# 20160428.net
KiCad netlist of a schematic drawn in Altium Designer
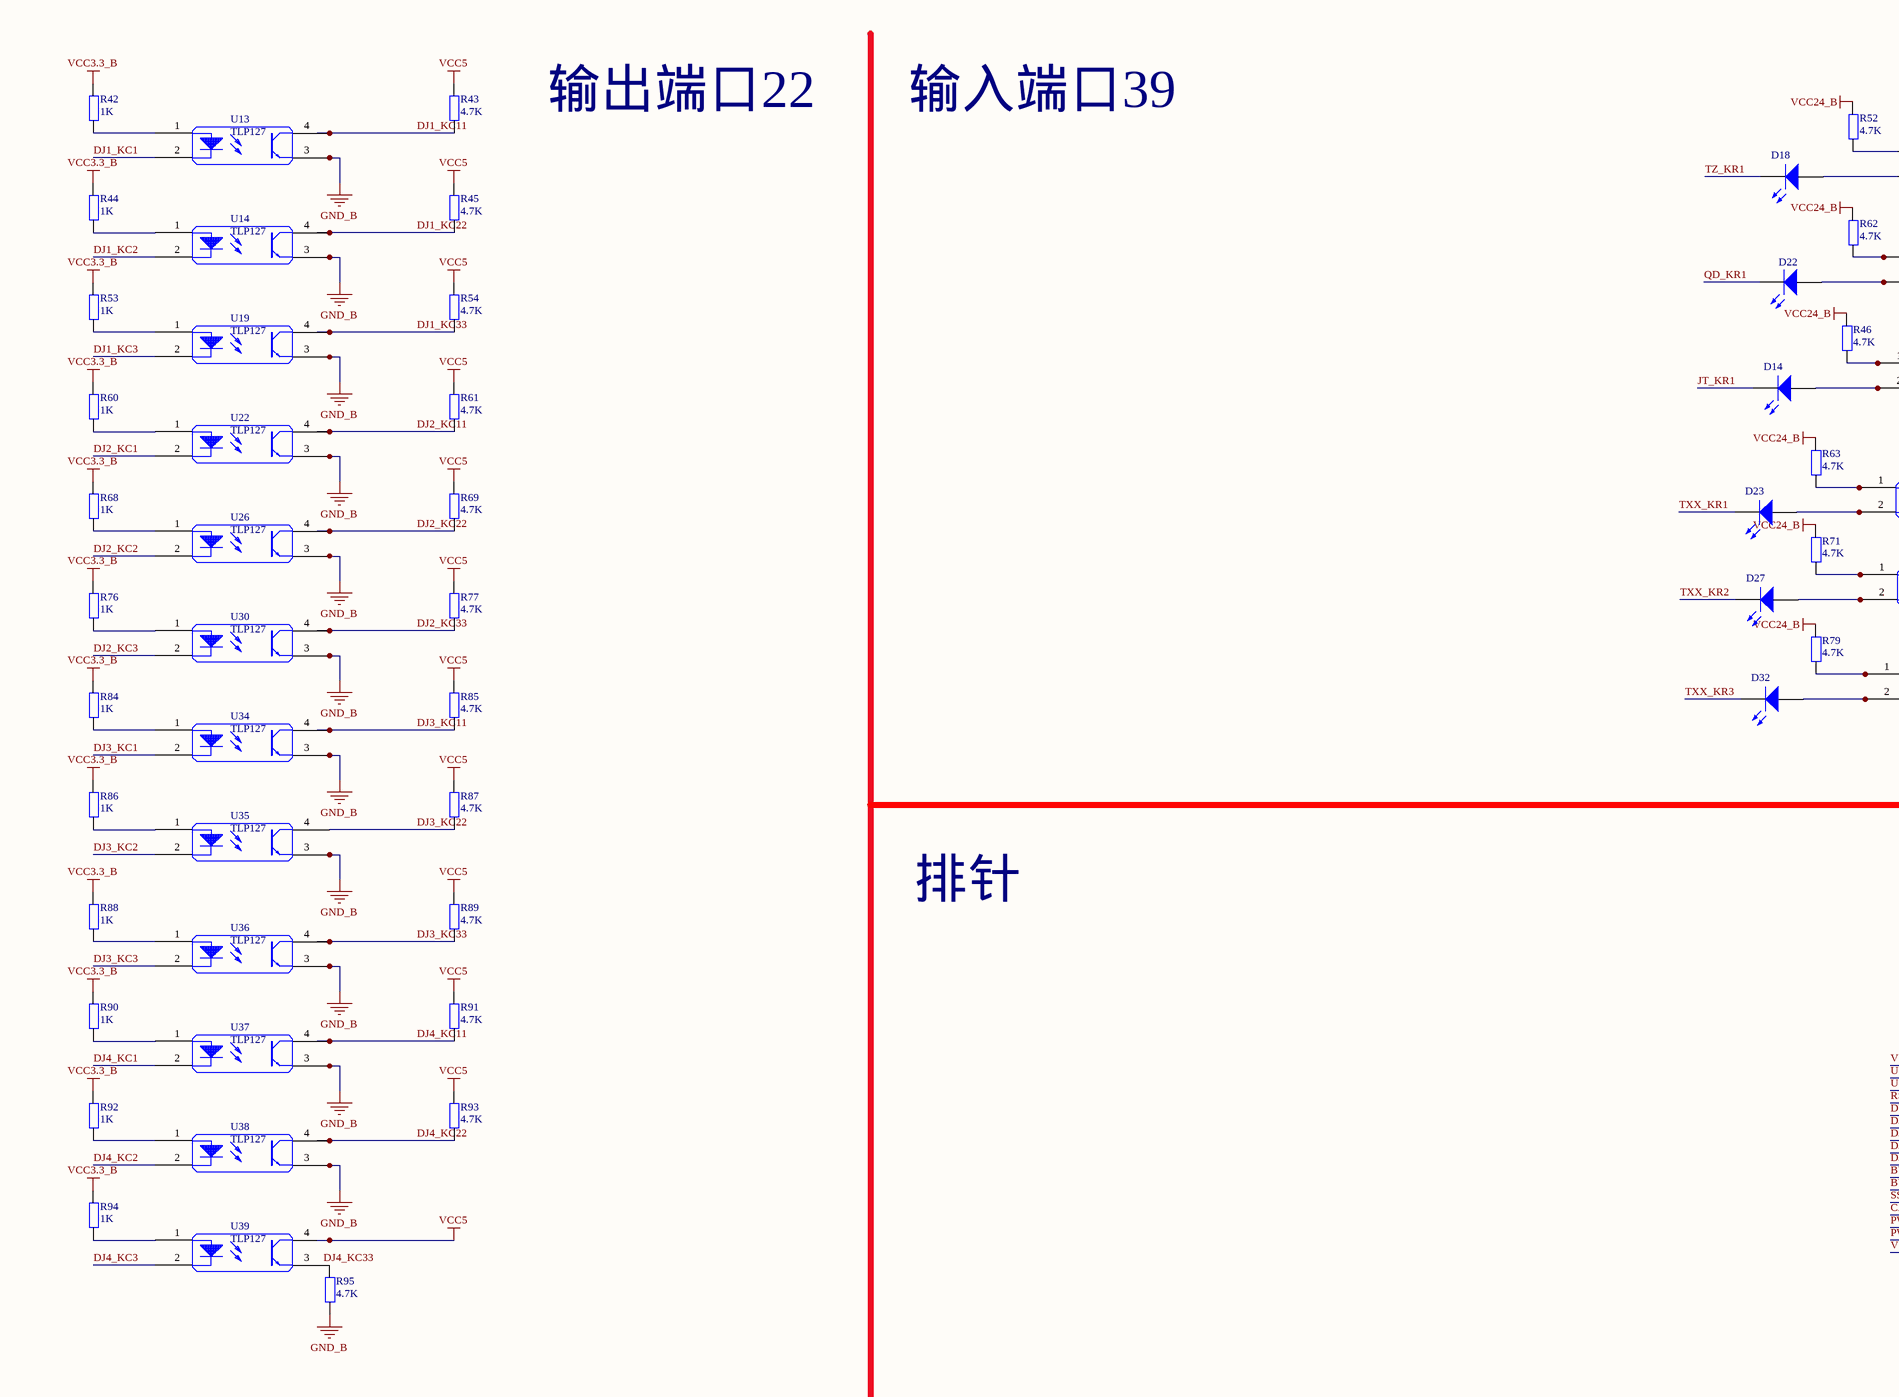
[diagram p0: 底板20160428.SchDoc, top left]
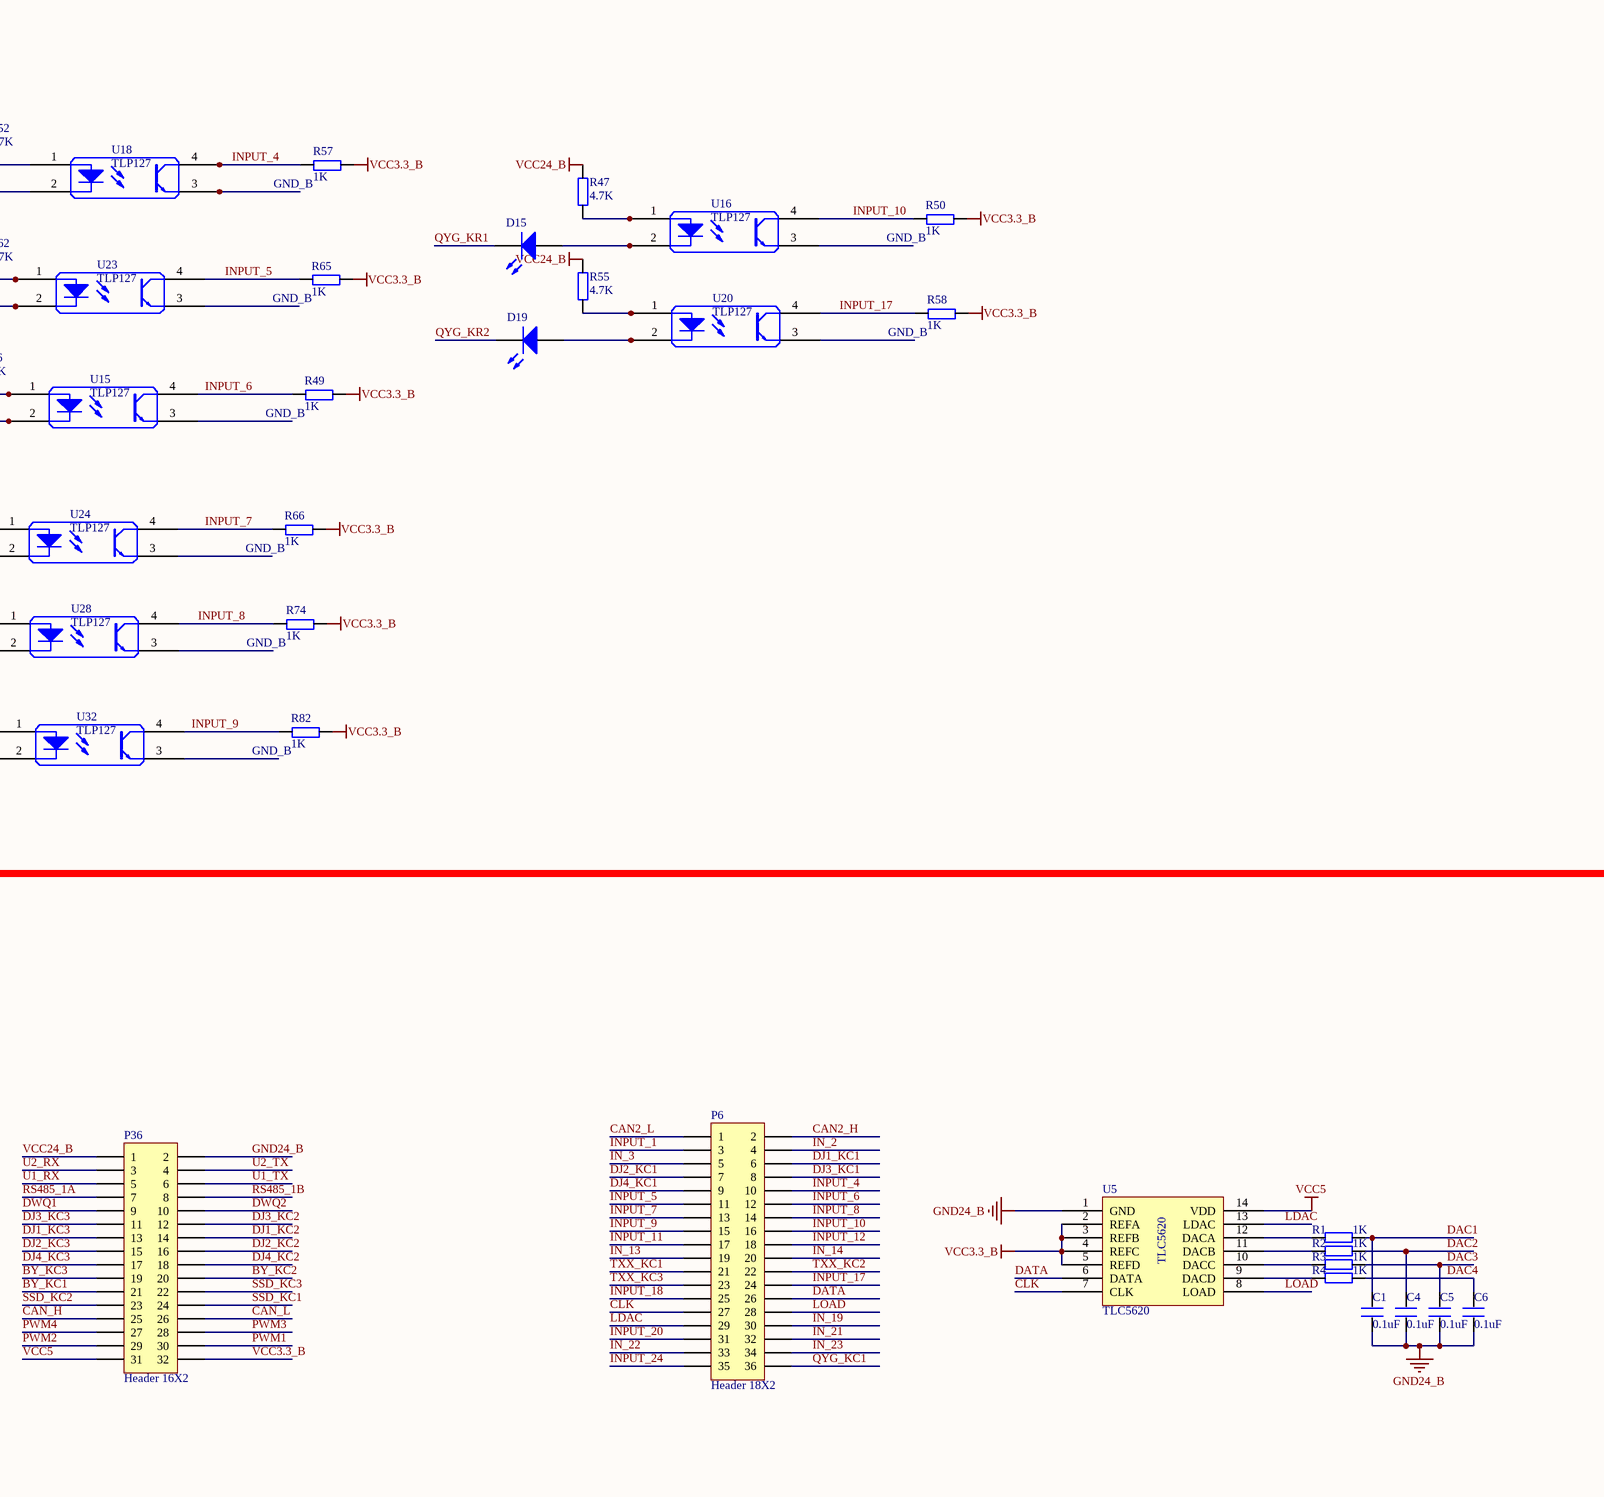
[diagram p1: 底板20160428.SchDoc, top right]
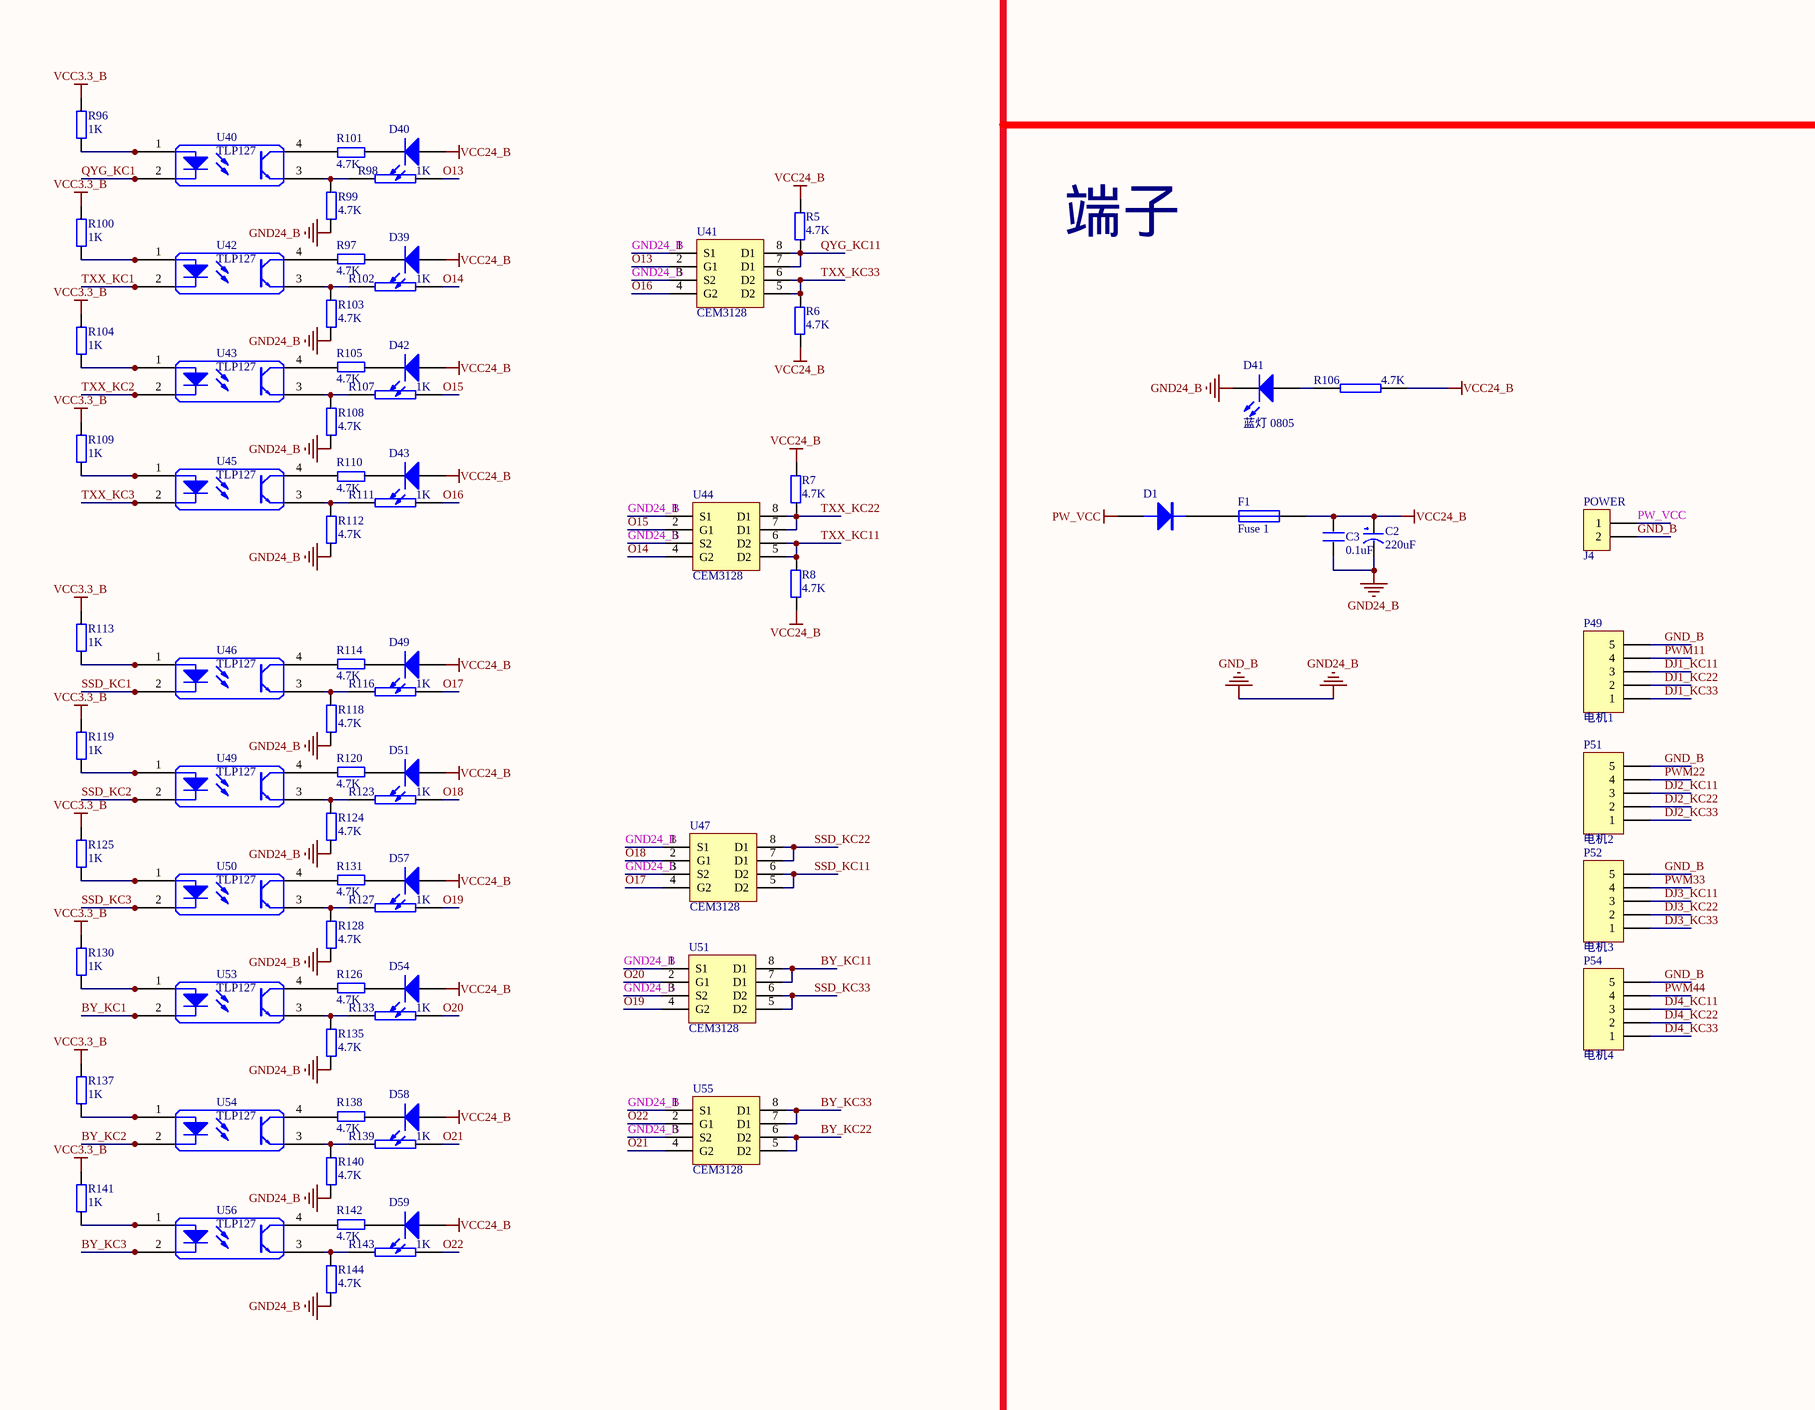
[diagram p2: 底板20160428.SchDoc, bottom left]
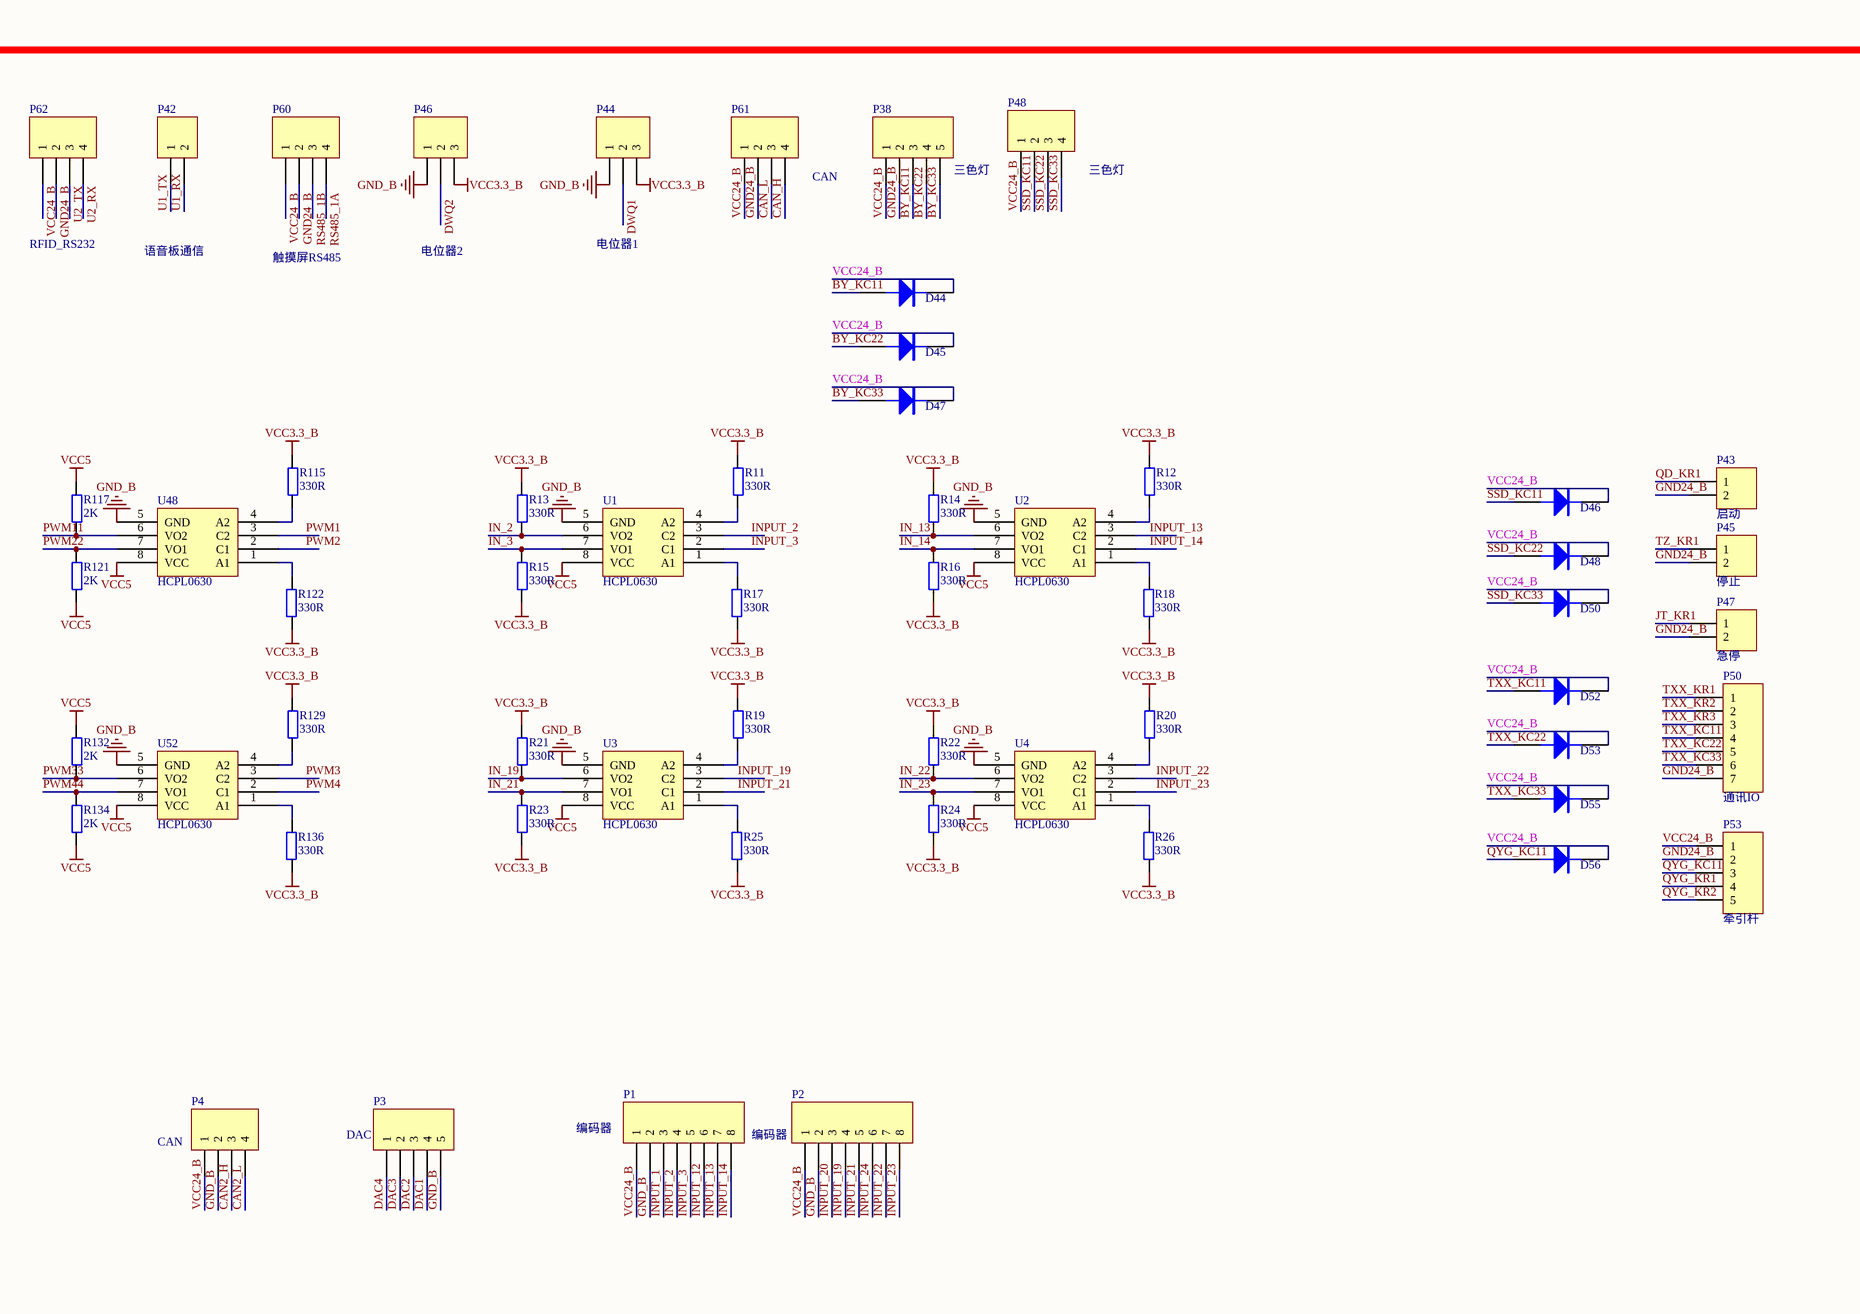
[diagram p3: 底板20160428.SchDoc, bottom right]

(export (version "E")
  (design (tool "Eeschema 10.0.6"))
  (components
    (comp (ref "C1") (value "0.1uF") (footprint "0603") (libsource (lib "WarShip V3_SCH") (part "C")))
    (comp (ref "C2") (value "220uF") (footprint "CC6.56.5") (libsource (lib "WarShip V3_SCH") (part "CAP")))
    (comp (ref "C3") (value "0.1uF") (footprint "0805") (libsource (lib "WarShip V3_SCH") (part "C")))
    (comp (ref "C4") (value "0.1uF") (footprint "0603") (libsource (lib "WarShip V3_SCH") (part "C")))
    (comp (ref "C5") (value "0.1uF") (footprint "0603") (libsource (lib "WarShip V3_SCH") (part "C")))
    (comp (ref "C6") (value "0.1uF") (footprint "0603") (libsource (lib "WarShip V3_SCH") (part "C")))
    (comp (ref "D1")
      (value "~")
      (footprint "LC-SMC(DO-214AB)_S2")
      (description "Diode")
      (libsource (lib "*") (part "DIODE"))
    )
    (comp (ref "D14")
      (value "LED0")
      (footprint "LC-0805_LED_S1")
      (description "Typical INFRARED GaAs LED")
      (fields (field (name "PUBLISHER") "Altium Limited"))
      (libsource (lib "继电器板_1") (part "LED0"))
    )
    (comp (ref "D15")
      (value "LED0")
      (footprint "LC-0805_LED_S1")
      (description "Typical INFRARED GaAs LED")
      (fields (field (name "PUBLISHER") "Altium Limited"))
      (libsource (lib "继电器板_1") (part "LED0"))
    )
    (comp (ref "D18")
      (value "LED0")
      (footprint "LC-0805_LED_S1")
      (description "Typical INFRARED GaAs LED")
      (fields (field (name "PUBLISHER") "Altium Limited"))
      (libsource (lib "继电器板_1") (part "LED0"))
    )
    (comp (ref "D19")
      (value "LED0")
      (footprint "LC-0805_LED_S1")
      (description "Typical INFRARED GaAs LED")
      (fields (field (name "PUBLISHER") "Altium Limited"))
      (libsource (lib "继电器板_1") (part "LED0"))
    )
    (comp (ref "D22")
      (value "LED0")
      (footprint "LC-0805_LED_S1")
      (description "Typical INFRARED GaAs LED")
      (fields (field (name "PUBLISHER") "Altium Limited"))
      (libsource (lib "继电器板_1") (part "LED0"))
    )
    (comp (ref "D23")
      (value "LED0")
      (footprint "LC-0805_LED_S1")
      (description "Typical INFRARED GaAs LED")
      (fields (field (name "PUBLISHER") "Altium Limited"))
      (libsource (lib "继电器板_1") (part "LED0"))
    )
    (comp (ref "D27")
      (value "LED0")
      (footprint "LC-0805_LED_S1")
      (description "Typical INFRARED GaAs LED")
      (fields (field (name "PUBLISHER") "Altium Limited"))
      (libsource (lib "继电器板_1") (part "LED0"))
    )
    (comp (ref "D32")
      (value "LED0")
      (footprint "LC-0805_LED_S1")
      (description "Typical INFRARED GaAs LED")
      (fields (field (name "PUBLISHER") "Altium Limited"))
      (libsource (lib "继电器板_1") (part "LED0"))
    )
    (comp (ref "D39")
      (value "LED0")
      (footprint "LC-0805_LED_S1")
      (description "Typical INFRARED GaAs LED")
      (fields (field (name "PUBLISHER") "Altium Limited"))
      (libsource (lib "继电器板_1") (part "LED0"))
    )
    (comp (ref "D40")
      (value "LED0")
      (footprint "LC-0805_LED_S1")
      (description "Typical INFRARED GaAs LED")
      (fields (field (name "PUBLISHER") "Altium Limited"))
      (libsource (lib "继电器板_1") (part "LED0"))
    )
    (comp (ref "D41")
      (value "蓝灯 0805")
      (footprint "0805_LED_S1")
      (description "发光二极管")
      (libsource (lib "Miscellaneous Devices LC - 副本") (part "0805 蓝灯"))
    )
    (comp (ref "D42")
      (value "LED0")
      (footprint "LC-0805_LED_S1")
      (description "Typical INFRARED GaAs LED")
      (fields (field (name "PUBLISHER") "Altium Limited"))
      (libsource (lib "继电器板_1") (part "LED0"))
    )
    (comp (ref "D43")
      (value "LED0")
      (footprint "LC-0805_LED_S1")
      (description "Typical INFRARED GaAs LED")
      (fields (field (name "PUBLISHER") "Altium Limited"))
      (libsource (lib "继电器板_1") (part "LED0"))
    )
    (comp (ref "D44")
      (value "~")
      (footprint "LC-LL-34")
      (description "Diode")
      (libsource (lib "*") (part "DIODE"))
    )
    (comp (ref "D45")
      (value "~")
      (footprint "LC-LL-34")
      (description "Diode")
      (libsource (lib "*") (part "DIODE"))
    )
    (comp (ref "D46")
      (value "~")
      (footprint "LC-LL-34")
      (description "Diode")
      (libsource (lib "*") (part "DIODE"))
    )
    (comp (ref "D47")
      (value "~")
      (footprint "LC-LL-34")
      (description "Diode")
      (libsource (lib "*") (part "DIODE"))
    )
    (comp (ref "D48")
      (value "~")
      (footprint "LC-LL-34")
      (description "Diode")
      (libsource (lib "*") (part "DIODE"))
    )
    (comp (ref "D49")
      (value "LED0")
      (footprint "LC-0805_LED_S1")
      (description "Typical INFRARED GaAs LED")
      (fields (field (name "PUBLISHER") "Altium Limited"))
      (libsource (lib "继电器板_1") (part "LED0"))
    )
    (comp (ref "D50")
      (value "~")
      (footprint "LC-LL-34")
      (description "Diode")
      (libsource (lib "*") (part "DIODE"))
    )
    (comp (ref "D51")
      (value "LED0")
      (footprint "LC-0805_LED_S1")
      (description "Typical INFRARED GaAs LED")
      (fields (field (name "PUBLISHER") "Altium Limited"))
      (libsource (lib "继电器板_1") (part "LED0"))
    )
    (comp (ref "D52")
      (value "~")
      (footprint "LC-LL-34")
      (description "Diode")
      (libsource (lib "*") (part "DIODE"))
    )
    (comp (ref "D53")
      (value "~")
      (footprint "LC-LL-34")
      (description "Diode")
      (libsource (lib "*") (part "DIODE"))
    )
    (comp (ref "D54")
      (value "LED0")
      (footprint "LC-0805_LED_S1")
      (description "Typical INFRARED GaAs LED")
      (fields (field (name "PUBLISHER") "Altium Limited"))
      (libsource (lib "继电器板_1") (part "LED0"))
    )
    (comp (ref "D55")
      (value "~")
      (footprint "LC-LL-34")
      (description "Diode")
      (libsource (lib "*") (part "DIODE"))
    )
    (comp (ref "D56")
      (value "~")
      (footprint "LC-LL-34")
      (description "Diode")
      (libsource (lib "*") (part "DIODE"))
    )
    (comp (ref "D57")
      (value "LED0")
      (footprint "LC-0805_LED_S1")
      (description "Typical INFRARED GaAs LED")
      (fields (field (name "PUBLISHER") "Altium Limited"))
      (libsource (lib "继电器板_1") (part "LED0"))
    )
    (comp (ref "D58")
      (value "LED0")
      (footprint "LC-0805_LED_S1")
      (description "Typical INFRARED GaAs LED")
      (fields (field (name "PUBLISHER") "Altium Limited"))
      (libsource (lib "继电器板_1") (part "LED0"))
    )
    (comp (ref "D59")
      (value "LED0")
      (footprint "LC-0805_LED_S1")
      (description "Typical INFRARED GaAs LED")
      (fields (field (name "PUBLISHER") "Altium Limited"))
      (libsource (lib "继电器板_1") (part "LED0"))
    )
    (comp (ref "F1")
      (value "Fuse 1")
      (footprint "1206")
      (description "Fuse")
      (fields (field (name "PUBLISHER") "Altium Limited"))
      (libsource (lib "Miscellaneous Devices") (part "Fuse 1"))
    )
    (comp (ref "J4")
      (value "CON2")
      (footprint "DZ-2-3.5")
      (description "Connector")
      (libsource (lib "*") (part "CON2"))
    )
    (comp (ref "P1")
      (value "编码器")
      (footprint "DZ-8-3.5")
      (description "Header, 8-Pin")
      (fields (field (name "PUBLISHER") "Altium Limited"))
      (libsource (lib "Miscellaneous Connectors") (part "Header 8"))
    )
    (comp (ref "P2")
      (value "编码器")
      (footprint "DZ-8-3.5")
      (description "Header, 8-Pin")
      (fields (field (name "PUBLISHER") "Altium Limited"))
      (libsource (lib "Miscellaneous Connectors") (part "Header 8"))
    )
    (comp (ref "P3")
      (value "DAC")
      (footprint "DZ-5-3.5")
      (description "Header, 5-Pin")
      (fields (field (name "PUBLISHER") "Altium Limited"))
      (libsource (lib "") (part "Header 5_1"))
    )
    (comp (ref "P4")
      (value "CAN")
      (footprint "DZ-4-3.5")
      (description "Header, 4-Pin")
      (fields (field (name "PUBLISHER") "Altium Limited"))
      (libsource (lib "Miscellaneous Connectors") (part "Header 4"))
    )
    (comp (ref "P6")
      (value "Header 18X2")
      (footprint "HDR2X18")
      (description "Header, 18-Pin, Dual row")
      (fields (field (name "PUBLISHER") "Altium Limited"))
      (libsource (lib "Miscellaneous Connectors") (part "Header 18X2"))
    )
    (comp (ref "P36")
      (value "Header 16X2")
      (footprint "HDR2X16")
      (description "Header, 16-Pin, Dual row")
      (fields (field (name "PUBLISHER") "Altium Limited"))
      (libsource (lib "Miscellaneous Connectors") (part "Header 16X2"))
    )
    (comp (ref "P38")
      (value "三色灯")
      (footprint "DZ-5-3.5")
      (description "Header, 5-Pin")
      (fields (field (name "PUBLISHER") "Altium Limited"))
      (libsource (lib "") (part "Header 5_1"))
    )
    (comp (ref "P42")
      (value "语音板通信")
      (footprint "DZ-2-3.5")
      (description "Header, 2-Pin")
      (fields (field (name "PUBLISHER") "Altium Limited"))
      (libsource (lib "") (part "Header 2_1"))
    )
    (comp (ref "P43")
      (value "启动")
      (footprint "DZ-2-3.5")
      (description "Header, 2-Pin")
      (fields (field (name "PUBLISHER") "Altium Limited"))
      (libsource (lib "Miscellaneous Connectors") (part "Header 2"))
    )
    (comp (ref "P44")
      (value "电位器1")
      (footprint "DZ-3-3.5")
      (description "Header, 3-Pin")
      (fields (field (name "PUBLISHER") "Altium Limited"))
      (libsource (lib "Miscellaneous Connectors") (part "Header 3"))
    )
    (comp (ref "P45")
      (value "停止")
      (footprint "DZ-2-3.5")
      (description "Header, 2-Pin")
      (fields (field (name "PUBLISHER") "Altium Limited"))
      (libsource (lib "Miscellaneous Connectors") (part "Header 2"))
    )
    (comp (ref "P46")
      (value "电位器2")
      (footprint "DZ-3-3.5")
      (description "Header, 3-Pin")
      (fields (field (name "PUBLISHER") "Altium Limited"))
      (libsource (lib "Miscellaneous Connectors") (part "Header 3"))
    )
    (comp (ref "P47")
      (value "急停")
      (footprint "DZ-2-3.5")
      (description "Header, 2-Pin")
      (fields (field (name "PUBLISHER") "Altium Limited"))
      (libsource (lib "Miscellaneous Connectors") (part "Header 2"))
    )
    (comp (ref "P48")
      (value "三色灯")
      (footprint "DZ-4-3.5")
      (description "Header, 4-Pin")
      (fields (field (name "PUBLISHER") "Altium Limited"))
      (libsource (lib "Miscellaneous Connectors") (part "Header 4"))
    )
    (comp (ref "P49")
      (value "电机1")
      (footprint "DZ-5-3.5")
      (description "Header, 5-Pin")
      (fields (field (name "PUBLISHER") "Altium Limited"))
      (libsource (lib "Miscellaneous Connectors") (part "Header 5"))
    )
    (comp (ref "P50")
      (value "通讯IO")
      (footprint "DZ-7-3.5")
      (description "Header, 7-Pin")
      (fields (field (name "PUBLISHER") "Altium Limited"))
      (libsource (lib "Miscellaneous Connectors") (part "Header 7"))
    )
    (comp (ref "P51")
      (value "电机2")
      (footprint "DZ-5-3.5")
      (description "Header, 5-Pin")
      (fields (field (name "PUBLISHER") "Altium Limited"))
      (libsource (lib "Miscellaneous Connectors") (part "Header 5"))
    )
    (comp (ref "P52")
      (value "电机3")
      (footprint "DZ-5-3.5")
      (description "Header, 5-Pin")
      (fields (field (name "PUBLISHER") "Altium Limited"))
      (libsource (lib "Miscellaneous Connectors") (part "Header 5"))
    )
    (comp (ref "P53")
      (value "牵引杆")
      (footprint "DZ-5-3.5")
      (description "Header, 5-Pin")
      (fields (field (name "PUBLISHER") "Altium Limited"))
      (libsource (lib "") (part "Header 5_2"))
    )
    (comp (ref "P54")
      (value "电机4")
      (footprint "DZ-5-3.5")
      (description "Header, 5-Pin")
      (fields (field (name "PUBLISHER") "Altium Limited"))
      (libsource (lib "Miscellaneous Connectors") (part "Header 5"))
    )
    (comp (ref "P60")
      (value "触摸屏RS485")
      (footprint "DZ-4-3.5")
      (description "Header, 4-Pin")
      (fields (field (name "PUBLISHER") "Altium Limited"))
      (libsource (lib "Miscellaneous Connectors") (part "Header 4"))
    )
    (comp (ref "P61")
      (value "CAN")
      (footprint "DZ-4-3.5")
      (description "Header, 4-Pin")
      (fields (field (name "PUBLISHER") "Altium Limited"))
      (libsource (lib "Miscellaneous Connectors") (part "Header 4"))
    )
    (comp (ref "P62")
      (value "RFID_RS232")
      (footprint "DZ-4-3.5")
      (description "Header, 4-Pin")
      (fields (field (name "PUBLISHER") "Altium Limited"))
      (libsource (lib "Miscellaneous Connectors") (part "Header 4"))
    )
    (comp (ref "R1") (value "1K") (footprint "0603") (libsource (lib "Explorer STM32F407封装库") (part "R_2")))
    (comp (ref "R2") (value "1K") (footprint "0603") (libsource (lib "Explorer STM32F407封装库") (part "R_2")))
    (comp (ref "R3") (value "1K") (footprint "0603") (libsource (lib "Explorer STM32F407封装库") (part "R_2")))
    (comp (ref "R4") (value "1K") (footprint "0603") (libsource (lib "Explorer STM32F407封装库") (part "R_2")))
    (comp (ref "R5") (value "4.7K") (footprint "0603") (libsource (lib "Explorer STM32F407封装库") (part "R_2")))
    (comp (ref "R6") (value "4.7K") (footprint "0603") (libsource (lib "Explorer STM32F407封装库") (part "R_2")))
    (comp (ref "R7") (value "4.7K") (footprint "0603") (libsource (lib "Explorer STM32F407封装库") (part "R_2")))
    (comp (ref "R8") (value "4.7K") (footprint "0603") (libsource (lib "Explorer STM32F407封装库") (part "R_2")))
    (comp (ref "R11")
      (value "330R")
      (footprint "0603")
      (libsource (lib "Explorer STM32F407封装库") (part "R_2"))
    )
    (comp (ref "R12")
      (value "330R")
      (footprint "0603")
      (libsource (lib "Explorer STM32F407封装库") (part "R_2"))
    )
    (comp (ref "R13")
      (value "330R")
      (footprint "0603")
      (libsource (lib "Explorer STM32F407封装库") (part "R_2"))
    )
    (comp (ref "R14")
      (value "330R")
      (footprint "0603")
      (libsource (lib "Explorer STM32F407封装库") (part "R_2"))
    )
    (comp (ref "R15")
      (value "330R")
      (footprint "0603")
      (libsource (lib "Explorer STM32F407封装库") (part "R_2"))
    )
    (comp (ref "R16")
      (value "330R")
      (footprint "0603")
      (libsource (lib "Explorer STM32F407封装库") (part "R_2"))
    )
    (comp (ref "R17")
      (value "330R")
      (footprint "0603")
      (libsource (lib "Explorer STM32F407封装库") (part "R_2"))
    )
    (comp (ref "R18")
      (value "330R")
      (footprint "0603")
      (libsource (lib "Explorer STM32F407封装库") (part "R_2"))
    )
    (comp (ref "R19")
      (value "330R")
      (footprint "0603")
      (libsource (lib "Explorer STM32F407封装库") (part "R_2"))
    )
    (comp (ref "R20")
      (value "330R")
      (footprint "0603")
      (libsource (lib "Explorer STM32F407封装库") (part "R_2"))
    )
    (comp (ref "R21")
      (value "330R")
      (footprint "0603")
      (libsource (lib "Explorer STM32F407封装库") (part "R_2"))
    )
    (comp (ref "R22")
      (value "330R")
      (footprint "0603")
      (libsource (lib "Explorer STM32F407封装库") (part "R_2"))
    )
    (comp (ref "R23")
      (value "330R")
      (footprint "0603")
      (libsource (lib "Explorer STM32F407封装库") (part "R_2"))
    )
    (comp (ref "R24")
      (value "330R")
      (footprint "0603")
      (libsource (lib "Explorer STM32F407封装库") (part "R_2"))
    )
    (comp (ref "R25")
      (value "330R")
      (footprint "0603")
      (libsource (lib "Explorer STM32F407封装库") (part "R_2"))
    )
    (comp (ref "R26")
      (value "330R")
      (footprint "0603")
      (libsource (lib "Explorer STM32F407封装库") (part "R_2"))
    )
    (comp (ref "R42") (value "1K") (footprint "0603") (libsource (lib "Explorer STM32F407封装库") (part "R_2")))
    (comp (ref "R43")
      (value "4.7K")
      (footprint "0603")
      (libsource (lib "Explorer STM32F407封装库") (part "R_2"))
    )
    (comp (ref "R44") (value "1K") (footprint "0603") (libsource (lib "Explorer STM32F407封装库") (part "R_2")))
    (comp (ref "R45")
      (value "4.7K")
      (footprint "0603")
      (libsource (lib "Explorer STM32F407封装库") (part "R_2"))
    )
    (comp (ref "R46")
      (value "4.7K")
      (footprint "0603")
      (libsource (lib "Explorer STM32F407封装库") (part "R_2"))
    )
    (comp (ref "R47")
      (value "4.7K")
      (footprint "0603")
      (libsource (lib "Explorer STM32F407封装库") (part "R_2"))
    )
    (comp (ref "R49") (value "1K") (footprint "0603") (libsource (lib "Explorer STM32F407封装库") (part "R_2")))
    (comp (ref "R50") (value "1K") (footprint "0603") (libsource (lib "Explorer STM32F407封装库") (part "R_2")))
    (comp (ref "R52")
      (value "4.7K")
      (footprint "0603")
      (libsource (lib "Explorer STM32F407封装库") (part "R_2"))
    )
    (comp (ref "R53") (value "1K") (footprint "0603") (libsource (lib "Explorer STM32F407封装库") (part "R_2")))
    (comp (ref "R54")
      (value "4.7K")
      (footprint "0603")
      (libsource (lib "Explorer STM32F407封装库") (part "R_2"))
    )
    (comp (ref "R55")
      (value "4.7K")
      (footprint "0603")
      (libsource (lib "Explorer STM32F407封装库") (part "R_2"))
    )
    (comp (ref "R57") (value "1K") (footprint "0603") (libsource (lib "Explorer STM32F407封装库") (part "R_2")))
    (comp (ref "R58") (value "1K") (footprint "0603") (libsource (lib "Explorer STM32F407封装库") (part "R_2")))
    (comp (ref "R60") (value "1K") (footprint "0603") (libsource (lib "Explorer STM32F407封装库") (part "R_2")))
    (comp (ref "R61")
      (value "4.7K")
      (footprint "0603")
      (libsource (lib "Explorer STM32F407封装库") (part "R_2"))
    )
    (comp (ref "R62")
      (value "4.7K")
      (footprint "0603")
      (libsource (lib "Explorer STM32F407封装库") (part "R_2"))
    )
    (comp (ref "R63")
      (value "4.7K")
      (footprint "0603")
      (libsource (lib "Explorer STM32F407封装库") (part "R_2"))
    )
    (comp (ref "R65") (value "1K") (footprint "0603") (libsource (lib "Explorer STM32F407封装库") (part "R_2")))
    (comp (ref "R66") (value "1K") (footprint "0603") (libsource (lib "Explorer STM32F407封装库") (part "R_2")))
    (comp (ref "R68") (value "1K") (footprint "0603") (libsource (lib "Explorer STM32F407封装库") (part "R_2")))
    (comp (ref "R69")
      (value "4.7K")
      (footprint "0603")
      (libsource (lib "Explorer STM32F407封装库") (part "R_2"))
    )
    (comp (ref "R71")
      (value "4.7K")
      (footprint "0603")
      (libsource (lib "Explorer STM32F407封装库") (part "R_2"))
    )
    (comp (ref "R74") (value "1K") (footprint "0603") (libsource (lib "Explorer STM32F407封装库") (part "R_2")))
    (comp (ref "R76") (value "1K") (footprint "0603") (libsource (lib "Explorer STM32F407封装库") (part "R_2")))
    (comp (ref "R77")
      (value "4.7K")
      (footprint "0603")
      (libsource (lib "Explorer STM32F407封装库") (part "R_2"))
    )
    (comp (ref "R79")
      (value "4.7K")
      (footprint "0603")
      (libsource (lib "Explorer STM32F407封装库") (part "R_2"))
    )
    (comp (ref "R82") (value "1K") (footprint "0603") (libsource (lib "Explorer STM32F407封装库") (part "R_2")))
    (comp (ref "R84") (value "1K") (footprint "0603") (libsource (lib "Explorer STM32F407封装库") (part "R_2")))
    (comp (ref "R85")
      (value "4.7K")
      (footprint "0603")
      (libsource (lib "Explorer STM32F407封装库") (part "R_2"))
    )
    (comp (ref "R86") (value "1K") (footprint "0603") (libsource (lib "Explorer STM32F407封装库") (part "R_2")))
    (comp (ref "R87")
      (value "4.7K")
      (footprint "0603")
      (libsource (lib "Explorer STM32F407封装库") (part "R_2"))
    )
    (comp (ref "R88") (value "1K") (footprint "0603") (libsource (lib "Explorer STM32F407封装库") (part "R_2")))
    (comp (ref "R89")
      (value "4.7K")
      (footprint "0603")
      (libsource (lib "Explorer STM32F407封装库") (part "R_2"))
    )
    (comp (ref "R90") (value "1K") (footprint "0603") (libsource (lib "Explorer STM32F407封装库") (part "R_2")))
    (comp (ref "R91")
      (value "4.7K")
      (footprint "0603")
      (libsource (lib "Explorer STM32F407封装库") (part "R_2"))
    )
    (comp (ref "R92") (value "1K") (footprint "0603") (libsource (lib "Explorer STM32F407封装库") (part "R_2")))
    (comp (ref "R93")
      (value "4.7K")
      (footprint "0603")
      (libsource (lib "Explorer STM32F407封装库") (part "R_2"))
    )
    (comp (ref "R94") (value "1K") (footprint "0603") (libsource (lib "Explorer STM32F407封装库") (part "R_2")))
    (comp (ref "R95")
      (value "4.7K")
      (footprint "0603")
      (libsource (lib "Explorer STM32F407封装库") (part "R_2"))
    )
    (comp (ref "R96") (value "1K") (footprint "0603") (libsource (lib "Explorer STM32F407封装库") (part "R_2")))
    (comp (ref "R97")
      (value "4.7K")
      (footprint "0603")
      (libsource (lib "Explorer STM32F407封装库") (part "R_2"))
    )
    (comp (ref "R98") (value "1K") (footprint "0603") (libsource (lib "*") (part "RES2")))
    (comp (ref "R99")
      (value "4.7K")
      (footprint "0603")
      (libsource (lib "Explorer STM32F407封装库") (part "R_2"))
    )
    (comp (ref "R100") (value "1K") (footprint "0603") (libsource (lib "Explorer STM32F407封装库") (part "R_2")))
    (comp (ref "R101")
      (value "4.7K")
      (footprint "0603")
      (libsource (lib "Explorer STM32F407封装库") (part "R_2"))
    )
    (comp (ref "R102") (value "1K") (footprint "0603") (libsource (lib "*") (part "RES2")))
    (comp (ref "R103")
      (value "4.7K")
      (footprint "0603")
      (libsource (lib "Explorer STM32F407封装库") (part "R_2"))
    )
    (comp (ref "R104") (value "1K") (footprint "0603") (libsource (lib "Explorer STM32F407封装库") (part "R_2")))
    (comp (ref "R105")
      (value "4.7K")
      (footprint "0603")
      (libsource (lib "Explorer STM32F407封装库") (part "R_2"))
    )
    (comp (ref "R106") (value "4.7K") (footprint "0603") (libsource (lib "*") (part "RES2")))
    (comp (ref "R107") (value "1K") (footprint "0603") (libsource (lib "*") (part "RES2")))
    (comp (ref "R108")
      (value "4.7K")
      (footprint "0603")
      (libsource (lib "Explorer STM32F407封装库") (part "R_2"))
    )
    (comp (ref "R109") (value "1K") (footprint "0603") (libsource (lib "Explorer STM32F407封装库") (part "R_2")))
    (comp (ref "R110")
      (value "4.7K")
      (footprint "0603")
      (libsource (lib "Explorer STM32F407封装库") (part "R_2"))
    )
    (comp (ref "R111") (value "1K") (footprint "0603") (libsource (lib "*") (part "RES2")))
    (comp (ref "R112")
      (value "4.7K")
      (footprint "0603")
      (libsource (lib "Explorer STM32F407封装库") (part "R_2"))
    )
    (comp (ref "R113") (value "1K") (footprint "0603") (libsource (lib "Explorer STM32F407封装库") (part "R_2")))
    (comp (ref "R114")
      (value "4.7K")
      (footprint "0603")
      (libsource (lib "Explorer STM32F407封装库") (part "R_2"))
    )
    (comp (ref "R115")
      (value "330R")
      (footprint "0603")
      (libsource (lib "Explorer STM32F407封装库") (part "R_2"))
    )
    (comp (ref "R116") (value "1K") (footprint "0603") (libsource (lib "*") (part "RES2")))
    (comp (ref "R117") (value "2K") (footprint "0603") (libsource (lib "Explorer STM32F407封装库") (part "R_2")))
    (comp (ref "R118")
      (value "4.7K")
      (footprint "0603")
      (libsource (lib "Explorer STM32F407封装库") (part "R_2"))
    )
    (comp (ref "R119") (value "1K") (footprint "0603") (libsource (lib "Explorer STM32F407封装库") (part "R_2")))
    (comp (ref "R120")
      (value "4.7K")
      (footprint "0603")
      (libsource (lib "Explorer STM32F407封装库") (part "R_2"))
    )
    (comp (ref "R121") (value "2K") (footprint "0603") (libsource (lib "Explorer STM32F407封装库") (part "R_2")))
    (comp (ref "R122")
      (value "330R")
      (footprint "0603")
      (libsource (lib "Explorer STM32F407封装库") (part "R_2"))
    )
    (comp (ref "R123") (value "1K") (footprint "0603") (libsource (lib "*") (part "RES2")))
    (comp (ref "R124")
      (value "4.7K")
      (footprint "0603")
      (libsource (lib "Explorer STM32F407封装库") (part "R_2"))
    )
    (comp (ref "R125") (value "1K") (footprint "0603") (libsource (lib "Explorer STM32F407封装库") (part "R_2")))
    (comp (ref "R126")
      (value "4.7K")
      (footprint "0603")
      (libsource (lib "Explorer STM32F407封装库") (part "R_2"))
    )
    (comp (ref "R127") (value "1K") (footprint "0603") (libsource (lib "*") (part "RES2")))
    (comp (ref "R128")
      (value "4.7K")
      (footprint "0603")
      (libsource (lib "Explorer STM32F407封装库") (part "R_2"))
    )
    (comp (ref "R129")
      (value "330R")
      (footprint "0603")
      (libsource (lib "Explorer STM32F407封装库") (part "R_2"))
    )
    (comp (ref "R130") (value "1K") (footprint "0603") (libsource (lib "Explorer STM32F407封装库") (part "R_2")))
    (comp (ref "R131")
      (value "4.7K")
      (footprint "0603")
      (libsource (lib "Explorer STM32F407封装库") (part "R_2"))
    )
    (comp (ref "R132") (value "2K") (footprint "0603") (libsource (lib "Explorer STM32F407封装库") (part "R_2")))
    (comp (ref "R133") (value "1K") (footprint "0603") (libsource (lib "*") (part "RES2")))
    (comp (ref "R134") (value "2K") (footprint "0603") (libsource (lib "Explorer STM32F407封装库") (part "R_2")))
    (comp (ref "R135")
      (value "4.7K")
      (footprint "0603")
      (libsource (lib "Explorer STM32F407封装库") (part "R_2"))
    )
    (comp (ref "R136")
      (value "330R")
      (footprint "0603")
      (libsource (lib "Explorer STM32F407封装库") (part "R_2"))
    )
    (comp (ref "R137") (value "1K") (footprint "0603") (libsource (lib "Explorer STM32F407封装库") (part "R_2")))
    (comp (ref "R138")
      (value "4.7K")
      (footprint "0603")
      (libsource (lib "Explorer STM32F407封装库") (part "R_2"))
    )
    (comp (ref "R139") (value "1K") (footprint "0603") (libsource (lib "*") (part "RES2")))
    (comp (ref "R140")
      (value "4.7K")
      (footprint "0603")
      (libsource (lib "Explorer STM32F407封装库") (part "R_2"))
    )
    (comp (ref "R141") (value "1K") (footprint "0603") (libsource (lib "Explorer STM32F407封装库") (part "R_2")))
    (comp (ref "R142")
      (value "4.7K")
      (footprint "0603")
      (libsource (lib "Explorer STM32F407封装库") (part "R_2"))
    )
    (comp (ref "R143") (value "1K") (footprint "0603") (libsource (lib "*") (part "RES2")))
    (comp (ref "R144")
      (value "4.7K")
      (footprint "0603")
      (libsource (lib "Explorer STM32F407封装库") (part "R_2"))
    )
    (comp (ref "U1") (value "HCPL0630") (footprint "SO-8") (libsource (lib "EXPLORER") (part "HCPL0630")))
    (comp (ref "U2") (value "HCPL0630") (footprint "SO-8") (libsource (lib "EXPLORER") (part "HCPL0630")))
    (comp (ref "U3") (value "HCPL0630") (footprint "SO-8") (libsource (lib "EXPLORER") (part "HCPL0630")))
    (comp (ref "U4") (value "HCPL0630") (footprint "SO-8") (libsource (lib "EXPLORER") (part "HCPL0630")))
    (comp (ref "U5")
      (value "TLC5620")
      (footprint "LC-SOIC-14_150mil")
      (libsource (lib "Schlib1") (part "Component_1"))
    )
    (comp (ref "U13") (value "TLP127") (footprint "LC-SOP-4_P2.54") (libsource (lib "*") (part "2701")))
    (comp (ref "U14") (value "TLP127") (footprint "LC-SOP-4_P2.54") (libsource (lib "*") (part "2701")))
    (comp (ref "U15") (value "TLP127") (footprint "LC-SOP-4_P2.54") (libsource (lib "*") (part "2701")))
    (comp (ref "U16") (value "TLP127") (footprint "LC-SOP-4_P2.54") (libsource (lib "*") (part "2701")))
    (comp (ref "U18") (value "TLP127") (footprint "LC-SOP-4_P2.54") (libsource (lib "*") (part "2701")))
    (comp (ref "U19") (value "TLP127") (footprint "LC-SOP-4_P2.54") (libsource (lib "*") (part "2701")))
    (comp (ref "U20") (value "TLP127") (footprint "LC-SOP-4_P2.54") (libsource (lib "*") (part "2701")))
    (comp (ref "U22") (value "TLP127") (footprint "LC-SOP-4_P2.54") (libsource (lib "*") (part "2701")))
    (comp (ref "U23") (value "TLP127") (footprint "LC-SOP-4_P2.54") (libsource (lib "*") (part "2701")))
    (comp (ref "U24") (value "TLP127") (footprint "LC-SOP-4_P2.54") (libsource (lib "*") (part "2701")))
    (comp (ref "U26") (value "TLP127") (footprint "LC-SOP-4_P2.54") (libsource (lib "*") (part "2701")))
    (comp (ref "U28") (value "TLP127") (footprint "LC-SOP-4_P2.54") (libsource (lib "*") (part "2701")))
    (comp (ref "U30") (value "TLP127") (footprint "LC-SOP-4_P2.54") (libsource (lib "*") (part "2701")))
    (comp (ref "U32") (value "TLP127") (footprint "LC-SOP-4_P2.54") (libsource (lib "*") (part "2701")))
    (comp (ref "U34") (value "TLP127") (footprint "LC-SOP-4_P2.54") (libsource (lib "*") (part "2701")))
    (comp (ref "U35") (value "TLP127") (footprint "LC-SOP-4_P2.54") (libsource (lib "*") (part "2701")))
    (comp (ref "U36") (value "TLP127") (footprint "LC-SOP-4_P2.54") (libsource (lib "*") (part "2701")))
    (comp (ref "U37") (value "TLP127") (footprint "LC-SOP-4_P2.54") (libsource (lib "*") (part "2701")))
    (comp (ref "U38") (value "TLP127") (footprint "LC-SOP-4_P2.54") (libsource (lib "*") (part "2701")))
    (comp (ref "U39") (value "TLP127") (footprint "LC-SOP-4_P2.54") (libsource (lib "*") (part "2701")))
    (comp (ref "U40") (value "TLP127") (footprint "LC-SOP-4_P2.54") (libsource (lib "*") (part "2701")))
    (comp (ref "U41") (value "CEM3128") (footprint "SO-8") (libsource (lib "*") (part "AF4920N")))
    (comp (ref "U42") (value "TLP127") (footprint "LC-SOP-4_P2.54") (libsource (lib "*") (part "2701")))
    (comp (ref "U43") (value "TLP127") (footprint "LC-SOP-4_P2.54") (libsource (lib "*") (part "2701")))
    (comp (ref "U44") (value "CEM3128") (footprint "SO-8") (libsource (lib "*") (part "AF4920N")))
    (comp (ref "U45") (value "TLP127") (footprint "LC-SOP-4_P2.54") (libsource (lib "*") (part "2701")))
    (comp (ref "U46") (value "TLP127") (footprint "LC-SOP-4_P2.54") (libsource (lib "*") (part "2701")))
    (comp (ref "U47") (value "CEM3128") (footprint "SO-8") (libsource (lib "*") (part "AF4920N")))
    (comp (ref "U48") (value "HCPL0630") (footprint "SO-8") (libsource (lib "EXPLORER") (part "HCPL0630")))
    (comp (ref "U49") (value "TLP127") (footprint "LC-SOP-4_P2.54") (libsource (lib "*") (part "2701")))
    (comp (ref "U50") (value "TLP127") (footprint "LC-SOP-4_P2.54") (libsource (lib "*") (part "2701")))
    (comp (ref "U51") (value "CEM3128") (footprint "SO-8") (libsource (lib "*") (part "AF4920N")))
    (comp (ref "U52") (value "HCPL0630") (footprint "SO-8") (libsource (lib "EXPLORER") (part "HCPL0630")))
    (comp (ref "U53") (value "TLP127") (footprint "LC-SOP-4_P2.54") (libsource (lib "*") (part "2701")))
    (comp (ref "U54") (value "TLP127") (footprint "LC-SOP-4_P2.54") (libsource (lib "*") (part "2701")))
    (comp (ref "U55") (value "CEM3128") (footprint "SO-8") (libsource (lib "*") (part "AF4920N")))
    (comp (ref "U56") (value "TLP127") (footprint "LC-SOP-4_P2.54") (libsource (lib "*") (part "2701")))
  )
  (nets
    (net (code "1") (name "/BY_KC1") (class "Default")
      (node (ref "P36") (pin "21") (pinfunction "21_21") (pintype "passive"))
      (node (ref "U53") (pin "2") (pintype "passive"))
    )
    (net (code "2") (name "/BY_KC2") (class "Default")
      (node (ref "P36") (pin "20") (pinfunction "20_20") (pintype "passive"))
      (node (ref "U54") (pin "2") (pintype "passive"))
    )
    (net (code "3") (name "/BY_KC3") (class "Default")
      (node (ref "P36") (pin "19") (pinfunction "19_19") (pintype "passive"))
      (node (ref "U56") (pin "2") (pintype "passive"))
    )
    (net (code "4") (name "/BY_KC11") (class "Default")
      (node (ref "D44") (pin "1") (pinfunction "A_1") (pintype "passive"))
      (node (ref "P38") (pin "3") (pinfunction "3_3") (pintype "passive"))
      (node (ref "U51") (pin "7") (pinfunction "D1_7") (pintype "passive"))
      (node (ref "U51") (pin "8") (pinfunction "D1_8") (pintype "passive"))
    )
    (net (code "5") (name "/BY_KC22") (class "Default")
      (node (ref "D45") (pin "1") (pinfunction "A_1") (pintype "passive"))
      (node (ref "P38") (pin "4") (pinfunction "4_4") (pintype "passive"))
      (node (ref "U55") (pin "5") (pinfunction "D2_5") (pintype "passive"))
      (node (ref "U55") (pin "6") (pinfunction "D2_6") (pintype "passive"))
    )
    (net (code "6") (name "/BY_KC33") (class "Default")
      (node (ref "D47") (pin "1") (pinfunction "A_1") (pintype "passive"))
      (node (ref "P38") (pin "5") (pinfunction "5_5") (pintype "passive"))
      (node (ref "U55") (pin "7") (pinfunction "D1_7") (pintype "passive"))
      (node (ref "U55") (pin "8") (pinfunction "D1_8") (pintype "passive"))
    )
    (net (code "7") (name "/CAN2_H") (class "Default")
      (node (ref "P4") (pin "3") (pinfunction "3_3") (pintype "passive"))
      (node (ref "P6") (pin "2") (pinfunction "2_2") (pintype "passive"))
    )
    (net (code "8") (name "/CAN2_L") (class "Default")
      (node (ref "P4") (pin "4") (pinfunction "4_4") (pintype "passive"))
      (node (ref "P6") (pin "1") (pinfunction "1_1") (pintype "passive"))
    )
    (net (code "9") (name "/CAN_H") (class "Default")
      (node (ref "P36") (pin "25") (pinfunction "25_25") (pintype "passive"))
      (node (ref "P61") (pin "4") (pinfunction "4_4") (pintype "passive"))
    )
    (net (code "10") (name "/CAN_L") (class "Default")
      (node (ref "P36") (pin "26") (pinfunction "26_26") (pintype "passive"))
      (node (ref "P61") (pin "3") (pinfunction "3_3") (pintype "passive"))
    )
    (net (code "11") (name "/CLK") (class "Default")
      (node (ref "P6") (pin "27") (pinfunction "27_27") (pintype "passive"))
      (node (ref "U5") (pin "7") (pinfunction "CLK_7") (pintype "passive"))
    )
    (net (code "12") (name "/DAC1") (class "Default")
      (node (ref "C1") (pin "2") (pintype "passive"))
      (node (ref "P3") (pin "4") (pinfunction "4_4") (pintype "passive"))
      (node (ref "R1") (pin "1") (pintype "passive"))
    )
    (net (code "13") (name "/DAC2") (class "Default")
      (node (ref "C4") (pin "2") (pintype "passive"))
      (node (ref "P3") (pin "3") (pinfunction "3_3") (pintype "passive"))
      (node (ref "R2") (pin "1") (pintype "passive"))
    )
    (net (code "14") (name "/DAC3") (class "Default")
      (node (ref "C5") (pin "2") (pintype "passive"))
      (node (ref "P3") (pin "2") (pinfunction "2_2") (pintype "passive"))
      (node (ref "R3") (pin "1") (pintype "passive"))
    )
    (net (code "15") (name "/DAC4") (class "Default")
      (node (ref "C6") (pin "2") (pintype "passive"))
      (node (ref "P3") (pin "1") (pinfunction "1_1") (pintype "passive"))
      (node (ref "R4") (pin "1") (pintype "passive"))
    )
    (net (code "16") (name "/DATA") (class "Default")
      (node (ref "P6") (pin "26") (pinfunction "26_26") (pintype "passive"))
      (node (ref "U5") (pin "6") (pinfunction "DATA_6") (pintype "passive"))
    )
    (net (code "17") (name "/DJ1_KC1") (class "Default")
      (node (ref "P6") (pin "6") (pinfunction "6_6") (pintype "passive"))
      (node (ref "U13") (pin "2") (pintype "passive"))
    )
    (net (code "18") (name "/DJ1_KC2") (class "Default")
      (node (ref "P36") (pin "14") (pinfunction "14_14") (pintype "passive"))
      (node (ref "U14") (pin "2") (pintype "passive"))
    )
    (net (code "19") (name "/DJ1_KC3") (class "Default")
      (node (ref "P36") (pin "13") (pinfunction "13_13") (pintype "passive"))
      (node (ref "U19") (pin "2") (pintype "passive"))
    )
    (net (code "20") (name "/DJ1_KC11") (class "Default")
      (node (ref "P49") (pin "3") (pinfunction "3_3") (pintype "passive"))
      (node (ref "R43") (pin "1") (pintype "passive"))
      (node (ref "U13") (pin "4") (pintype "passive"))
    )
    (net (code "21") (name "/DJ1_KC22") (class "Default")
      (node (ref "P49") (pin "2") (pinfunction "2_2") (pintype "passive"))
      (node (ref "R45") (pin "1") (pintype "passive"))
      (node (ref "U14") (pin "4") (pintype "passive"))
    )
    (net (code "22") (name "/DJ1_KC33") (class "Default")
      (node (ref "P49") (pin "1") (pinfunction "1_1") (pintype "passive"))
      (node (ref "R54") (pin "1") (pintype "passive"))
      (node (ref "U19") (pin "4") (pintype "passive"))
    )
    (net (code "23") (name "/DJ2_KC1") (class "Default")
      (node (ref "P6") (pin "7") (pinfunction "7_7") (pintype "passive"))
      (node (ref "U22") (pin "2") (pintype "passive"))
    )
    (net (code "24") (name "/DJ2_KC2") (class "Default")
      (node (ref "P36") (pin "16") (pinfunction "16_16") (pintype "passive"))
      (node (ref "U26") (pin "2") (pintype "passive"))
    )
    (net (code "25") (name "/DJ2_KC3") (class "Default")
      (node (ref "P36") (pin "15") (pinfunction "15_15") (pintype "passive"))
      (node (ref "U30") (pin "2") (pintype "passive"))
    )
    (net (code "26") (name "/DJ2_KC11") (class "Default")
      (node (ref "P51") (pin "3") (pinfunction "3_3") (pintype "passive"))
      (node (ref "R61") (pin "1") (pintype "passive"))
      (node (ref "U22") (pin "4") (pintype "passive"))
    )
    (net (code "27") (name "/DJ2_KC22") (class "Default")
      (node (ref "P51") (pin "2") (pinfunction "2_2") (pintype "passive"))
      (node (ref "R69") (pin "1") (pintype "passive"))
      (node (ref "U26") (pin "4") (pintype "passive"))
    )
    (net (code "28") (name "/DJ2_KC33") (class "Default")
      (node (ref "P51") (pin "1") (pinfunction "1_1") (pintype "passive"))
      (node (ref "R77") (pin "1") (pintype "passive"))
      (node (ref "U30") (pin "4") (pintype "passive"))
    )
    (net (code "29") (name "/DJ3_KC1") (class "Default")
      (node (ref "P6") (pin "8") (pinfunction "8_8") (pintype "passive"))
      (node (ref "U34") (pin "2") (pintype "passive"))
    )
    (net (code "30") (name "/DJ3_KC2") (class "Default")
      (node (ref "P36") (pin "12") (pinfunction "12_12") (pintype "passive"))
      (node (ref "U35") (pin "2") (pintype "passive"))
    )
    (net (code "31") (name "/DJ3_KC3") (class "Default")
      (node (ref "P36") (pin "11") (pinfunction "11_11") (pintype "passive"))
      (node (ref "U36") (pin "2") (pintype "passive"))
    )
    (net (code "32") (name "/DJ3_KC11") (class "Default")
      (node (ref "P52") (pin "3") (pinfunction "3_3") (pintype "passive"))
      (node (ref "R85") (pin "1") (pintype "passive"))
      (node (ref "U34") (pin "4") (pintype "passive"))
    )
    (net (code "33") (name "/DJ3_KC22") (class "Default")
      (node (ref "P52") (pin "2") (pinfunction "2_2") (pintype "passive"))
      (node (ref "R87") (pin "1") (pintype "passive"))
      (node (ref "U35") (pin "4") (pintype "passive"))
    )
    (net (code "34") (name "/DJ3_KC33") (class "Default")
      (node (ref "P52") (pin "1") (pinfunction "1_1") (pintype "passive"))
      (node (ref "R89") (pin "1") (pintype "passive"))
      (node (ref "U36") (pin "4") (pintype "passive"))
    )
    (net (code "35") (name "/DJ4_KC1") (class "Default")
      (node (ref "P6") (pin "9") (pinfunction "9_9") (pintype "passive"))
      (node (ref "U37") (pin "2") (pintype "passive"))
    )
    (net (code "36") (name "/DJ4_KC2") (class "Default")
      (node (ref "P36") (pin "18") (pinfunction "18_18") (pintype "passive"))
      (node (ref "U38") (pin "2") (pintype "passive"))
    )
    (net (code "37") (name "/DJ4_KC3") (class "Default")
      (node (ref "P36") (pin "17") (pinfunction "17_17") (pintype "passive"))
      (node (ref "U39") (pin "2") (pintype "passive"))
    )
    (net (code "38") (name "/DJ4_KC11") (class "Default")
      (node (ref "P54") (pin "3") (pinfunction "3_3") (pintype "passive"))
      (node (ref "R91") (pin "1") (pintype "passive"))
      (node (ref "U37") (pin "4") (pintype "passive"))
    )
    (net (code "39") (name "/DJ4_KC22") (class "Default")
      (node (ref "P54") (pin "2") (pinfunction "2_2") (pintype "passive"))
      (node (ref "R93") (pin "1") (pintype "passive"))
      (node (ref "U38") (pin "4") (pintype "passive"))
    )
    (net (code "40") (name "/DJ4_KC33") (class "Default")
      (node (ref "P54") (pin "1") (pinfunction "1_1") (pintype "passive"))
    )
    (net (code "41") (name "/DWQ1") (class "Default")
      (node (ref "P36") (pin "9") (pinfunction "9_9") (pintype "passive"))
      (node (ref "P44") (pin "2") (pinfunction "2_2") (pintype "passive"))
    )
    (net (code "42") (name "/DWQ2") (class "Default")
      (node (ref "P36") (pin "10") (pinfunction "10_10") (pintype "passive"))
      (node (ref "P46") (pin "2") (pinfunction "2_2") (pintype "passive"))
    )
    (net (code "43") (name "/INPUT_1") (class "Default")
      (node (ref "P1") (pin "3") (pinfunction "3_3") (pintype "passive"))
      (node (ref "P6") (pin "3") (pinfunction "3_3") (pintype "passive"))
    )
    (net (code "44") (name "/INPUT_2") (class "Default")
      (node (ref "P1") (pin "4") (pinfunction "4_4") (pintype "passive"))
      (node (ref "U1") (pin "3") (pinfunction "C2_3") (pintype "passive"))
    )
    (net (code "45") (name "/INPUT_3") (class "Default")
      (node (ref "P1") (pin "5") (pinfunction "5_5") (pintype "passive"))
      (node (ref "U1") (pin "2") (pinfunction "C1_2") (pintype "passive"))
    )
    (net (code "46") (name "/INPUT_4") (class "Default")
      (node (ref "P6") (pin "10") (pinfunction "10_10") (pintype "passive"))
      (node (ref "R57") (pin "1") (pintype "passive"))
      (node (ref "U18") (pin "4") (pintype "passive"))
    )
    (net (code "47") (name "/INPUT_5") (class "Default")
      (node (ref "P6") (pin "11") (pinfunction "11_11") (pintype "passive"))
      (node (ref "R65") (pin "1") (pintype "passive"))
      (node (ref "U23") (pin "4") (pintype "passive"))
    )
    (net (code "48") (name "/INPUT_6") (class "Default")
      (node (ref "P6") (pin "12") (pinfunction "12_12") (pintype "passive"))
      (node (ref "R49") (pin "1") (pintype "passive"))
      (node (ref "U15") (pin "4") (pintype "passive"))
    )
    (net (code "49") (name "/INPUT_7") (class "Default")
      (node (ref "P6") (pin "13") (pinfunction "13_13") (pintype "passive"))
      (node (ref "R66") (pin "1") (pintype "passive"))
      (node (ref "U24") (pin "4") (pintype "passive"))
    )
    (net (code "50") (name "/INPUT_8") (class "Default")
      (node (ref "P6") (pin "14") (pinfunction "14_14") (pintype "passive"))
      (node (ref "R74") (pin "1") (pintype "passive"))
      (node (ref "U28") (pin "4") (pintype "passive"))
    )
    (net (code "51") (name "/INPUT_9") (class "Default")
      (node (ref "P6") (pin "15") (pinfunction "15_15") (pintype "passive"))
      (node (ref "R82") (pin "1") (pintype "passive"))
      (node (ref "U32") (pin "4") (pintype "passive"))
    )
    (net (code "52") (name "/INPUT_10") (class "Default")
      (node (ref "P6") (pin "16") (pinfunction "16_16") (pintype "passive"))
      (node (ref "R50") (pin "1") (pintype "passive"))
      (node (ref "U16") (pin "4") (pintype "passive"))
    )
    (net (code "53") (name "/INPUT_11") (class "Default")
      (node (ref "P6") (pin "17") (pinfunction "17_17") (pintype "passive"))
    )
    (net (code "54") (name "/INPUT_12") (class "Default")
      (node (ref "P1") (pin "6") (pinfunction "6_6") (pintype "passive"))
      (node (ref "P6") (pin "18") (pinfunction "18_18") (pintype "passive"))
    )
    (net (code "55") (name "/INPUT_13") (class "Default")
      (node (ref "P1") (pin "7") (pinfunction "7_7") (pintype "passive"))
      (node (ref "U2") (pin "3") (pinfunction "C2_3") (pintype "passive"))
    )
    (net (code "56") (name "/INPUT_14") (class "Default")
      (node (ref "P1") (pin "8") (pinfunction "8_8") (pintype "passive"))
      (node (ref "U2") (pin "2") (pinfunction "C1_2") (pintype "passive"))
    )
    (net (code "57") (name "/INPUT_17") (class "Default")
      (node (ref "P6") (pin "24") (pinfunction "24_24") (pintype "passive"))
      (node (ref "R58") (pin "1") (pintype "passive"))
      (node (ref "U20") (pin "4") (pintype "passive"))
    )
    (net (code "58") (name "/INPUT_18") (class "Default")
      (node (ref "P6") (pin "25") (pinfunction "25_25") (pintype "passive"))
    )
    (net (code "59") (name "/INPUT_19") (class "Default")
      (node (ref "P2") (pin "4") (pinfunction "4_4") (pintype "passive"))
      (node (ref "U3") (pin "3") (pinfunction "C2_3") (pintype "passive"))
    )
    (net (code "60") (name "/INPUT_20") (class "Default")
      (node (ref "P2") (pin "3") (pinfunction "3_3") (pintype "passive"))
      (node (ref "P6") (pin "31") (pinfunction "31_31") (pintype "passive"))
    )
    (net (code "61") (name "/INPUT_21") (class "Default")
      (node (ref "P2") (pin "5") (pinfunction "5_5") (pintype "passive"))
      (node (ref "U3") (pin "2") (pinfunction "C1_2") (pintype "passive"))
    )
    (net (code "62") (name "/INPUT_22") (class "Default")
      (node (ref "P2") (pin "7") (pinfunction "7_7") (pintype "passive"))
      (node (ref "U4") (pin "3") (pinfunction "C2_3") (pintype "passive"))
    )
    (net (code "63") (name "/INPUT_23") (class "Default")
      (node (ref "P2") (pin "8") (pinfunction "8_8") (pintype "passive"))
      (node (ref "U4") (pin "2") (pinfunction "C1_2") (pintype "passive"))
    )
    (net (code "64") (name "/INPUT_24") (class "Default")
      (node (ref "P2") (pin "6") (pinfunction "6_6") (pintype "passive"))
      (node (ref "P6") (pin "35") (pinfunction "35_35") (pintype "passive"))
    )
    (net (code "65") (name "/IN_2") (class "Default")
      (node (ref "P6") (pin "4") (pinfunction "4_4") (pintype "passive"))
      (node (ref "R13") (pin "1") (pintype "passive"))
      (node (ref "U1") (pin "6") (pinfunction "VO2_6") (pintype "passive"))
    )
    (net (code "66") (name "/IN_3") (class "Default")
      (node (ref "P6") (pin "5") (pinfunction "5_5") (pintype "passive"))
      (node (ref "R15") (pin "2") (pintype "passive"))
      (node (ref "U1") (pin "7") (pinfunction "VO1_7") (pintype "passive"))
    )
    (net (code "67") (name "/IN_13") (class "Default")
      (node (ref "P6") (pin "19") (pinfunction "19_19") (pintype "passive"))
      (node (ref "R14") (pin "1") (pintype "passive"))
      (node (ref "U2") (pin "6") (pinfunction "VO2_6") (pintype "passive"))
    )
    (net (code "68") (name "/IN_14") (class "Default")
      (node (ref "P6") (pin "20") (pinfunction "20_20") (pintype "passive"))
      (node (ref "R16") (pin "2") (pintype "passive"))
      (node (ref "U2") (pin "7") (pinfunction "VO1_7") (pintype "passive"))
    )
    (net (code "69") (name "/IN_19") (class "Default")
      (node (ref "P6") (pin "30") (pinfunction "30_30") (pintype "passive"))
      (node (ref "R21") (pin "1") (pintype "passive"))
      (node (ref "U3") (pin "6") (pinfunction "VO2_6") (pintype "passive"))
    )
    (net (code "70") (name "/IN_21") (class "Default")
      (node (ref "P6") (pin "32") (pinfunction "32_32") (pintype "passive"))
      (node (ref "R23") (pin "2") (pintype "passive"))
      (node (ref "U3") (pin "7") (pinfunction "VO1_7") (pintype "passive"))
    )
    (net (code "71") (name "/IN_22") (class "Default")
      (node (ref "P6") (pin "33") (pinfunction "33_33") (pintype "passive"))
      (node (ref "R22") (pin "1") (pintype "passive"))
      (node (ref "U4") (pin "6") (pinfunction "VO2_6") (pintype "passive"))
    )
    (net (code "72") (name "/IN_23") (class "Default")
      (node (ref "P6") (pin "34") (pinfunction "34_34") (pintype "passive"))
      (node (ref "R24") (pin "2") (pintype "passive"))
      (node (ref "U4") (pin "7") (pinfunction "VO1_7") (pintype "passive"))
    )
    (net (code "73") (name "/JT_KR1") (class "Default")
      (node (ref "D14") (pin "K") (pinfunction "K_K") (pintype "passive"))
      (node (ref "P47") (pin "1") (pinfunction "1_1") (pintype "passive"))
    )
    (net (code "74") (name "/LDAC") (class "Default")
      (node (ref "P6") (pin "29") (pinfunction "29_29") (pintype "passive"))
      (node (ref "U5") (pin "13") (pinfunction "LDAC_13") (pintype "passive"))
    )
    (net (code "75") (name "/LOAD") (class "Default")
      (node (ref "P6") (pin "28") (pinfunction "28_28") (pintype "passive"))
      (node (ref "U5") (pin "8") (pinfunction "LOAD_8") (pintype "passive"))
    )
    (net (code "76") (name "/O13") (class "Default")
      (node (ref "R98") (pin "1") (pinfunction "1_1") (pintype "passive"))
      (node (ref "U41") (pin "2") (pinfunction "G1_2") (pintype "passive"))
    )
    (net (code "77") (name "/O14") (class "Default")
      (node (ref "R102") (pin "1") (pinfunction "1_1") (pintype "passive"))
      (node (ref "U44") (pin "4") (pinfunction "G2_4") (pintype "passive"))
    )
    (net (code "78") (name "/O15") (class "Default")
      (node (ref "R107") (pin "1") (pinfunction "1_1") (pintype "passive"))
      (node (ref "U44") (pin "2") (pinfunction "G1_2") (pintype "passive"))
    )
    (net (code "79") (name "/O16") (class "Default")
      (node (ref "R111") (pin "1") (pinfunction "1_1") (pintype "passive"))
      (node (ref "U41") (pin "4") (pinfunction "G2_4") (pintype "passive"))
    )
    (net (code "80") (name "/O17") (class "Default")
      (node (ref "R116") (pin "1") (pinfunction "1_1") (pintype "passive"))
      (node (ref "U47") (pin "4") (pinfunction "G2_4") (pintype "passive"))
    )
    (net (code "81") (name "/O18") (class "Default")
      (node (ref "R123") (pin "1") (pinfunction "1_1") (pintype "passive"))
      (node (ref "U47") (pin "2") (pinfunction "G1_2") (pintype "passive"))
    )
    (net (code "82") (name "/O19") (class "Default")
      (node (ref "R127") (pin "1") (pinfunction "1_1") (pintype "passive"))
      (node (ref "U51") (pin "4") (pinfunction "G2_4") (pintype "passive"))
    )
    (net (code "83") (name "/O20") (class "Default")
      (node (ref "R133") (pin "1") (pinfunction "1_1") (pintype "passive"))
      (node (ref "U51") (pin "2") (pinfunction "G1_2") (pintype "passive"))
    )
    (net (code "84") (name "/O21") (class "Default")
      (node (ref "R139") (pin "1") (pinfunction "1_1") (pintype "passive"))
      (node (ref "U55") (pin "4") (pinfunction "G2_4") (pintype "passive"))
    )
    (net (code "85") (name "/O22") (class "Default")
      (node (ref "R143") (pin "1") (pinfunction "1_1") (pintype "passive"))
      (node (ref "U55") (pin "2") (pinfunction "G1_2") (pintype "passive"))
    )
    (net (code "86") (name "/PWM1") (class "Default")
      (node (ref "P36") (pin "30") (pinfunction "30_30") (pintype "passive"))
      (node (ref "U48") (pin "3") (pinfunction "C2_3") (pintype "passive"))
    )
    (net (code "87") (name "/PWM2") (class "Default")
      (node (ref "P36") (pin "29") (pinfunction "29_29") (pintype "passive"))
      (node (ref "U48") (pin "2") (pinfunction "C1_2") (pintype "passive"))
    )
    (net (code "88") (name "/PWM3") (class "Default")
      (node (ref "P36") (pin "28") (pinfunction "28_28") (pintype "passive"))
      (node (ref "U52") (pin "3") (pinfunction "C2_3") (pintype "passive"))
    )
    (net (code "89") (name "/PWM4") (class "Default")
      (node (ref "P36") (pin "27") (pinfunction "27_27") (pintype "passive"))
      (node (ref "U52") (pin "2") (pinfunction "C1_2") (pintype "passive"))
    )
    (net (code "90") (name "/PWM11") (class "Default")
      (node (ref "P49") (pin "4") (pinfunction "4_4") (pintype "passive"))
      (node (ref "R117") (pin "1") (pintype "passive"))
      (node (ref "U48") (pin "6") (pinfunction "VO2_6") (pintype "passive"))
    )
    (net (code "91") (name "/PWM22") (class "Default")
      (node (ref "P51") (pin "4") (pinfunction "4_4") (pintype "passive"))
      (node (ref "R121") (pin "2") (pintype "passive"))
      (node (ref "U48") (pin "7") (pinfunction "VO1_7") (pintype "passive"))
    )
    (net (code "92") (name "/PWM33") (class "Default")
      (node (ref "P52") (pin "4") (pinfunction "4_4") (pintype "passive"))
      (node (ref "R132") (pin "1") (pintype "passive"))
      (node (ref "U52") (pin "6") (pinfunction "VO2_6") (pintype "passive"))
    )
    (net (code "93") (name "/PWM44") (class "Default")
      (node (ref "P54") (pin "4") (pinfunction "4_4") (pintype "passive"))
      (node (ref "R134") (pin "2") (pintype "passive"))
      (node (ref "U52") (pin "7") (pinfunction "VO1_7") (pintype "passive"))
    )
    (net (code "94") (name "/QD_KR1") (class "Default")
      (node (ref "D22") (pin "K") (pinfunction "K_K") (pintype "passive"))
      (node (ref "P43") (pin "1") (pinfunction "1_1") (pintype "passive"))
    )
    (net (code "95") (name "/QYG_KC1") (class "Default")
      (node (ref "P6") (pin "36") (pinfunction "36_36") (pintype "passive"))
      (node (ref "U40") (pin "2") (pintype "passive"))
    )
    (net (code "96") (name "/QYG_KC11") (class "Default")
      (node (ref "D56") (pin "1") (pinfunction "A_1") (pintype "passive"))
      (node (ref "P53") (pin "3") (pinfunction "3_3") (pintype "passive"))
      (node (ref "R5") (pin "2") (pintype "passive"))
      (node (ref "U41") (pin "7") (pinfunction "D1_7") (pintype "passive"))
      (node (ref "U41") (pin "8") (pinfunction "D1_8") (pintype "passive"))
    )
    (net (code "97") (name "/QYG_KR1") (class "Default")
      (node (ref "D15") (pin "K") (pinfunction "K_K") (pintype "passive"))
      (node (ref "P53") (pin "4") (pinfunction "4_4") (pintype "passive"))
    )
    (net (code "98") (name "/QYG_KR2") (class "Default")
      (node (ref "D19") (pin "K") (pinfunction "K_K") (pintype "passive"))
      (node (ref "P53") (pin "5") (pinfunction "5_5") (pintype "passive"))
    )
    (net (code "99") (name "/RS485_1A") (class "Default")
      (node (ref "P36") (pin "7") (pinfunction "7_7") (pintype "passive"))
      (node (ref "P60") (pin "4") (pinfunction "4_4") (pintype "passive"))
    )
    (net (code "100") (name "/RS485_1B") (class "Default")
      (node (ref "P36") (pin "8") (pinfunction "8_8") (pintype "passive"))
      (node (ref "P60") (pin "3") (pinfunction "3_3") (pintype "passive"))
    )
    (net (code "101") (name "/SSD_KC1") (class "Default")
      (node (ref "P36") (pin "24") (pinfunction "24_24") (pintype "passive"))
      (node (ref "U46") (pin "2") (pintype "passive"))
    )
    (net (code "102") (name "/SSD_KC2") (class "Default")
      (node (ref "P36") (pin "23") (pinfunction "23_23") (pintype "passive"))
      (node (ref "U49") (pin "2") (pintype "passive"))
    )
    (net (code "103") (name "/SSD_KC3") (class "Default")
      (node (ref "P36") (pin "22") (pinfunction "22_22") (pintype "passive"))
      (node (ref "U50") (pin "2") (pintype "passive"))
    )
    (net (code "104") (name "/SSD_KC11") (class "Default")
      (node (ref "D46") (pin "1") (pinfunction "A_1") (pintype "passive"))
      (node (ref "P48") (pin "2") (pinfunction "2_2") (pintype "passive"))
      (node (ref "U47") (pin "5") (pinfunction "D2_5") (pintype "passive"))
      (node (ref "U47") (pin "6") (pinfunction "D2_6") (pintype "passive"))
    )
    (net (code "105") (name "/SSD_KC22") (class "Default")
      (node (ref "D48") (pin "1") (pinfunction "A_1") (pintype "passive"))
      (node (ref "P48") (pin "3") (pinfunction "3_3") (pintype "passive"))
      (node (ref "U47") (pin "7") (pinfunction "D1_7") (pintype "passive"))
      (node (ref "U47") (pin "8") (pinfunction "D1_8") (pintype "passive"))
    )
    (net (code "106") (name "/SSD_KC33") (class "Default")
      (node (ref "D50") (pin "1") (pinfunction "A_1") (pintype "passive"))
      (node (ref "P48") (pin "4") (pinfunction "4_4") (pintype "passive"))
      (node (ref "U51") (pin "5") (pinfunction "D2_5") (pintype "passive"))
      (node (ref "U51") (pin "6") (pinfunction "D2_6") (pintype "passive"))
    )
    (net (code "107") (name "/TXX_KC1") (class "Default")
      (node (ref "P6") (pin "21") (pinfunction "21_21") (pintype "passive"))
      (node (ref "U42") (pin "2") (pintype "passive"))
    )
    (net (code "108") (name "/TXX_KC2") (class "Default")
      (node (ref "P6") (pin "22") (pinfunction "22_22") (pintype "passive"))
      (node (ref "U43") (pin "2") (pintype "passive"))
    )
    (net (code "109") (name "/TXX_KC3") (class "Default")
      (node (ref "P6") (pin "23") (pinfunction "23_23") (pintype "passive"))
      (node (ref "U45") (pin "2") (pintype "passive"))
    )
    (net (code "110") (name "/TXX_KC11") (class "Default")
      (node (ref "D52") (pin "1") (pinfunction "A_1") (pintype "passive"))
      (node (ref "P50") (pin "4") (pinfunction "4_4") (pintype "passive"))
      (node (ref "R8") (pin "1") (pintype "passive"))
      (node (ref "U44") (pin "5") (pinfunction "D2_5") (pintype "passive"))
      (node (ref "U44") (pin "6") (pinfunction "D2_6") (pintype "passive"))
    )
    (net (code "111") (name "/TXX_KC22") (class "Default")
      (node (ref "D53") (pin "1") (pinfunction "A_1") (pintype "passive"))
      (node (ref "P50") (pin "5") (pinfunction "5_5") (pintype "passive"))
      (node (ref "R7") (pin "2") (pintype "passive"))
      (node (ref "U44") (pin "7") (pinfunction "D1_7") (pintype "passive"))
      (node (ref "U44") (pin "8") (pinfunction "D1_8") (pintype "passive"))
    )
    (net (code "112") (name "/TXX_KC33") (class "Default")
      (node (ref "D55") (pin "1") (pinfunction "A_1") (pintype "passive"))
      (node (ref "P50") (pin "6") (pinfunction "6_6") (pintype "passive"))
      (node (ref "R6") (pin "1") (pintype "passive"))
      (node (ref "U41") (pin "5") (pinfunction "D2_5") (pintype "passive"))
      (node (ref "U41") (pin "6") (pinfunction "D2_6") (pintype "passive"))
    )
    (net (code "113") (name "/TXX_KR1") (class "Default")
      (node (ref "D23") (pin "K") (pinfunction "K_K") (pintype "passive"))
      (node (ref "P50") (pin "1") (pinfunction "1_1") (pintype "passive"))
    )
    (net (code "114") (name "/TXX_KR2") (class "Default")
      (node (ref "D27") (pin "K") (pinfunction "K_K") (pintype "passive"))
      (node (ref "P50") (pin "2") (pinfunction "2_2") (pintype "passive"))
    )
    (net (code "115") (name "/TXX_KR3") (class "Default")
      (node (ref "D32") (pin "K") (pinfunction "K_K") (pintype "passive"))
      (node (ref "P50") (pin "3") (pinfunction "3_3") (pintype "passive"))
    )
    (net (code "116") (name "/TZ_KR1") (class "Default")
      (node (ref "D18") (pin "K") (pinfunction "K_K") (pintype "passive"))
      (node (ref "P45") (pin "1") (pinfunction "1_1") (pintype "passive"))
    )
    (net (code "117") (name "/U1_RX") (class "Default")
      (node (ref "P36") (pin "5") (pinfunction "5_5") (pintype "passive"))
      (node (ref "P42") (pin "2") (pinfunction "2_2") (pintype "passive"))
    )
    (net (code "118") (name "/U1_TX") (class "Default")
      (node (ref "P36") (pin "6") (pinfunction "6_6") (pintype "passive"))
      (node (ref "P42") (pin "1") (pinfunction "1_1") (pintype "passive"))
    )
    (net (code "119") (name "/U2_RX") (class "Default")
      (node (ref "P36") (pin "3") (pinfunction "3_3") (pintype "passive"))
      (node (ref "P62") (pin "4") (pinfunction "4_4") (pintype "passive"))
    )
    (net (code "120") (name "/U2_TX") (class "Default")
      (node (ref "P36") (pin "4") (pinfunction "4_4") (pintype "passive"))
      (node (ref "P62") (pin "3") (pinfunction "3_3") (pintype "passive"))
    )
    (net (code "121") (name "GND24_B") (class "Default")
      (node (ref "C1") (pin "1") (pintype "passive"))
      (node (ref "C2") (pin "2") (pinfunction "GND_2") (pintype "passive"))
      (node (ref "C3") (pin "2") (pintype "passive"))
      (node (ref "C4") (pin "1") (pintype "passive"))
      (node (ref "C5") (pin "1") (pintype "passive"))
      (node (ref "C6") (pin "1") (pintype "passive"))
      (node (ref "D41") (pin "K") (pinfunction "K_K") (pintype "passive"))
      (node (ref "J4") (pin "2") (pinfunction "2_2") (pintype "passive"))
      (node (ref "P1") (pin "2") (pinfunction "2_2") (pintype "passive"))
      (node (ref "P2") (pin "2") (pinfunction "2_2") (pintype "passive"))
      (node (ref "P3") (pin "5") (pinfunction "5_5") (pintype "passive"))
      (node (ref "P36") (pin "2") (pinfunction "2_2") (pintype "passive"))
      (node (ref "P38") (pin "2") (pinfunction "2_2") (pintype "passive"))
      (node (ref "P4") (pin "2") (pinfunction "2_2") (pintype "passive"))
      (node (ref "P43") (pin "2") (pinfunction "2_2") (pintype "passive"))
      (node (ref "P44") (pin "1") (pinfunction "1_1") (pintype "passive"))
      (node (ref "P45") (pin "2") (pinfunction "2_2") (pintype "passive"))
      (node (ref "P46") (pin "1") (pinfunction "1_1") (pintype "passive"))
      (node (ref "P47") (pin "2") (pinfunction "2_2") (pintype "passive"))
      (node (ref "P49") (pin "5") (pinfunction "5_5") (pintype "passive"))
      (node (ref "P50") (pin "7") (pinfunction "7_7") (pintype "passive"))
      (node (ref "P51") (pin "5") (pinfunction "5_5") (pintype "passive"))
      (node (ref "P52") (pin "5") (pinfunction "5_5") (pintype "passive"))
      (node (ref "P53") (pin "2") (pinfunction "2_2") (pintype "passive"))
      (node (ref "P54") (pin "5") (pinfunction "5_5") (pintype "passive"))
      (node (ref "P60") (pin "2") (pinfunction "2_2") (pintype "passive"))
      (node (ref "P61") (pin "2") (pinfunction "2_2") (pintype "passive"))
      (node (ref "P62") (pin "2") (pinfunction "2_2") (pintype "passive"))
      (node (ref "R103") (pin "1") (pintype "passive"))
      (node (ref "R108") (pin "1") (pintype "passive"))
      (node (ref "R112") (pin "1") (pintype "passive"))
      (node (ref "R118") (pin "1") (pintype "passive"))
      (node (ref "R124") (pin "1") (pintype "passive"))
      (node (ref "R128") (pin "1") (pintype "passive"))
      (node (ref "R135") (pin "1") (pintype "passive"))
      (node (ref "R140") (pin "1") (pintype "passive"))
      (node (ref "R144") (pin "1") (pintype "passive"))
      (node (ref "R95") (pin "1") (pintype "passive"))
      (node (ref "R99") (pin "1") (pintype "passive"))
      (node (ref "U1") (pin "5") (pinfunction "GND_5") (pintype "passive"))
      (node (ref "U13") (pin "3") (pintype "passive"))
      (node (ref "U14") (pin "3") (pintype "passive"))
      (node (ref "U15") (pin "3") (pintype "passive"))
      (node (ref "U16") (pin "3") (pintype "passive"))
      (node (ref "U18") (pin "3") (pintype "passive"))
      (node (ref "U19") (pin "3") (pintype "passive"))
      (node (ref "U2") (pin "5") (pinfunction "GND_5") (pintype "passive"))
      (node (ref "U20") (pin "3") (pintype "passive"))
      (node (ref "U22") (pin "3") (pintype "passive"))
      (node (ref "U23") (pin "3") (pintype "passive"))
      (node (ref "U24") (pin "3") (pintype "passive"))
      (node (ref "U26") (pin "3") (pintype "passive"))
      (node (ref "U28") (pin "3") (pintype "passive"))
      (node (ref "U3") (pin "5") (pinfunction "GND_5") (pintype "passive"))
      (node (ref "U30") (pin "3") (pintype "passive"))
      (node (ref "U32") (pin "3") (pintype "passive"))
      (node (ref "U34") (pin "3") (pintype "passive"))
      (node (ref "U35") (pin "3") (pintype "passive"))
      (node (ref "U36") (pin "3") (pintype "passive"))
      (node (ref "U37") (pin "3") (pintype "passive"))
      (node (ref "U38") (pin "3") (pintype "passive"))
      (node (ref "U4") (pin "5") (pinfunction "GND_5") (pintype "passive"))
      (node (ref "U41") (pin "1") (pinfunction "S1_1") (pintype "passive"))
      (node (ref "U41") (pin "3") (pinfunction "S2_3") (pintype "passive"))
      (node (ref "U44") (pin "1") (pinfunction "S1_1") (pintype "passive"))
      (node (ref "U44") (pin "3") (pinfunction "S2_3") (pintype "passive"))
      (node (ref "U47") (pin "1") (pinfunction "S1_1") (pintype "passive"))
      (node (ref "U47") (pin "3") (pinfunction "S2_3") (pintype "passive"))
      (node (ref "U48") (pin "5") (pinfunction "GND_5") (pintype "passive"))
      (node (ref "U5") (pin "1") (pinfunction "GND_1") (pintype "passive"))
      (node (ref "U51") (pin "1") (pinfunction "S1_1") (pintype "passive"))
      (node (ref "U51") (pin "3") (pinfunction "S2_3") (pintype "passive"))
      (node (ref "U52") (pin "5") (pinfunction "GND_5") (pintype "passive"))
      (node (ref "U55") (pin "1") (pinfunction "S1_1") (pintype "passive"))
      (node (ref "U55") (pin "3") (pinfunction "S2_3") (pintype "passive"))
    )
    (net (code "122") (name "Net-(D1-K)") (class "Default")
      (node (ref "D1") (pin "2") (pinfunction "K_2") (pintype "passive"))
      (node (ref "F1") (pin "1") (pinfunction "1_1") (pintype "passive"))
    )
    (net (code "123") (name "Net-(D14-PadA)") (class "Default")
      (node (ref "D14") (pin "A") (pinfunction "A_A") (pintype "passive"))
      (node (ref "U15") (pin "2") (pintype "passive"))
    )
    (net (code "124") (name "Net-(D15-PadA)") (class "Default")
      (node (ref "D15") (pin "A") (pinfunction "A_A") (pintype "passive"))
      (node (ref "U16") (pin "2") (pintype "passive"))
    )
    (net (code "125") (name "Net-(D18-PadA)") (class "Default")
      (node (ref "D18") (pin "A") (pinfunction "A_A") (pintype "passive"))
      (node (ref "U18") (pin "2") (pintype "passive"))
    )
    (net (code "126") (name "Net-(D19-PadA)") (class "Default")
      (node (ref "D19") (pin "A") (pinfunction "A_A") (pintype "passive"))
      (node (ref "U20") (pin "2") (pintype "passive"))
    )
    (net (code "127") (name "Net-(D22-PadA)") (class "Default")
      (node (ref "D22") (pin "A") (pinfunction "A_A") (pintype "passive"))
      (node (ref "U23") (pin "2") (pintype "passive"))
    )
    (net (code "128") (name "Net-(D23-PadA)") (class "Default")
      (node (ref "D23") (pin "A") (pinfunction "A_A") (pintype "passive"))
      (node (ref "U24") (pin "2") (pintype "passive"))
    )
    (net (code "129") (name "Net-(D27-PadA)") (class "Default")
      (node (ref "D27") (pin "A") (pinfunction "A_A") (pintype "passive"))
      (node (ref "U28") (pin "2") (pintype "passive"))
    )
    (net (code "130") (name "Net-(D32-PadA)") (class "Default")
      (node (ref "D32") (pin "A") (pinfunction "A_A") (pintype "passive"))
      (node (ref "U32") (pin "2") (pintype "passive"))
    )
    (net (code "131") (name "Net-(D39-PadK)") (class "Default")
      (node (ref "D39") (pin "K") (pinfunction "K_K") (pintype "passive"))
      (node (ref "R97") (pin "1") (pintype "passive"))
    )
    (net (code "132") (name "Net-(D40-PadK)") (class "Default")
      (node (ref "D40") (pin "K") (pinfunction "K_K") (pintype "passive"))
      (node (ref "R101") (pin "2") (pintype "passive"))
    )
    (net (code "133") (name "Net-(D41-PadA)") (class "Default")
      (node (ref "D41") (pin "A") (pinfunction "A_A") (pintype "passive"))
      (node (ref "R106") (pin "2") (pinfunction "2_2") (pintype "passive"))
    )
    (net (code "134") (name "Net-(D42-PadK)") (class "Default")
      (node (ref "D42") (pin "K") (pinfunction "K_K") (pintype "passive"))
      (node (ref "R105") (pin "1") (pintype "passive"))
    )
    (net (code "135") (name "Net-(D43-PadK)") (class "Default")
      (node (ref "D43") (pin "K") (pinfunction "K_K") (pintype "passive"))
      (node (ref "R110") (pin "2") (pintype "passive"))
    )
    (net (code "136") (name "Net-(D49-PadK)") (class "Default")
      (node (ref "D49") (pin "K") (pinfunction "K_K") (pintype "passive"))
      (node (ref "R114") (pin "1") (pintype "passive"))
    )
    (net (code "137") (name "Net-(D51-PadK)") (class "Default")
      (node (ref "D51") (pin "K") (pinfunction "K_K") (pintype "passive"))
      (node (ref "R120") (pin "1") (pintype "passive"))
    )
    (net (code "138") (name "Net-(D54-PadK)") (class "Default")
      (node (ref "D54") (pin "K") (pinfunction "K_K") (pintype "passive"))
      (node (ref "R126") (pin "1") (pintype "passive"))
    )
    (net (code "139") (name "Net-(D57-PadK)") (class "Default")
      (node (ref "D57") (pin "K") (pinfunction "K_K") (pintype "passive"))
      (node (ref "R131") (pin "1") (pintype "passive"))
    )
    (net (code "140") (name "Net-(D58-PadK)") (class "Default")
      (node (ref "D58") (pin "K") (pinfunction "K_K") (pintype "passive"))
      (node (ref "R138") (pin "1") (pintype "passive"))
    )
    (net (code "141") (name "Net-(D59-PadK)") (class "Default")
      (node (ref "D59") (pin "K") (pinfunction "K_K") (pintype "passive"))
      (node (ref "R142") (pin "1") (pintype "passive"))
    )
    (net (code "142") (name "Net-(R42-Pad1)") (class "Default")
      (node (ref "R42") (pin "1") (pintype "passive"))
      (node (ref "U13") (pin "1") (pintype "passive"))
    )
    (net (code "143") (name "Net-(R44-Pad1)") (class "Default")
      (node (ref "R44") (pin "1") (pintype "passive"))
      (node (ref "U14") (pin "1") (pintype "passive"))
    )
    (net (code "144") (name "Net-(R46-Pad1)") (class "Default")
      (node (ref "R46") (pin "1") (pintype "passive"))
      (node (ref "U15") (pin "1") (pintype "passive"))
    )
    (net (code "145") (name "Net-(R47-Pad1)") (class "Default")
      (node (ref "R47") (pin "1") (pintype "passive"))
      (node (ref "U16") (pin "1") (pintype "passive"))
    )
    (net (code "146") (name "Net-(R52-Pad1)") (class "Default")
      (node (ref "R52") (pin "1") (pintype "passive"))
      (node (ref "U18") (pin "1") (pintype "passive"))
    )
    (net (code "147") (name "Net-(R53-Pad1)") (class "Default")
      (node (ref "R53") (pin "1") (pintype "passive"))
      (node (ref "U19") (pin "1") (pintype "passive"))
    )
    (net (code "148") (name "Net-(R55-Pad1)") (class "Default")
      (node (ref "R55") (pin "1") (pintype "passive"))
      (node (ref "U20") (pin "1") (pintype "passive"))
    )
    (net (code "149") (name "Net-(R60-Pad1)") (class "Default")
      (node (ref "R60") (pin "1") (pintype "passive"))
      (node (ref "U22") (pin "1") (pintype "passive"))
    )
    (net (code "150") (name "Net-(R62-Pad1)") (class "Default")
      (node (ref "R62") (pin "1") (pintype "passive"))
      (node (ref "U23") (pin "1") (pintype "passive"))
    )
    (net (code "151") (name "Net-(R63-Pad1)") (class "Default")
      (node (ref "R63") (pin "1") (pintype "passive"))
      (node (ref "U24") (pin "1") (pintype "passive"))
    )
    (net (code "152") (name "Net-(R68-Pad1)") (class "Default")
      (node (ref "R68") (pin "1") (pintype "passive"))
      (node (ref "U26") (pin "1") (pintype "passive"))
    )
    (net (code "153") (name "Net-(R71-Pad1)") (class "Default")
      (node (ref "R71") (pin "1") (pintype "passive"))
      (node (ref "U28") (pin "1") (pintype "passive"))
    )
    (net (code "154") (name "Net-(R76-Pad1)") (class "Default")
      (node (ref "R76") (pin "1") (pintype "passive"))
      (node (ref "U30") (pin "1") (pintype "passive"))
    )
    (net (code "155") (name "Net-(R79-Pad1)") (class "Default")
      (node (ref "R79") (pin "1") (pintype "passive"))
      (node (ref "U32") (pin "1") (pintype "passive"))
    )
    (net (code "156") (name "Net-(R84-Pad1)") (class "Default")
      (node (ref "R84") (pin "1") (pintype "passive"))
      (node (ref "U34") (pin "1") (pintype "passive"))
    )
    (net (code "157") (name "Net-(R86-Pad1)") (class "Default")
      (node (ref "R86") (pin "1") (pintype "passive"))
      (node (ref "U35") (pin "1") (pintype "passive"))
    )
    (net (code "158") (name "Net-(R88-Pad1)") (class "Default")
      (node (ref "R88") (pin "1") (pintype "passive"))
      (node (ref "U36") (pin "1") (pintype "passive"))
    )
    (net (code "159") (name "Net-(R90-Pad1)") (class "Default")
      (node (ref "R90") (pin "1") (pintype "passive"))
      (node (ref "U37") (pin "1") (pintype "passive"))
    )
    (net (code "160") (name "Net-(R92-Pad1)") (class "Default")
      (node (ref "R92") (pin "1") (pintype "passive"))
      (node (ref "U38") (pin "1") (pintype "passive"))
    )
    (net (code "161") (name "Net-(R94-Pad1)") (class "Default")
      (node (ref "R94") (pin "1") (pintype "passive"))
      (node (ref "U39") (pin "1") (pintype "passive"))
    )
    (net (code "162") (name "Net-(R95-Pad2)") (class "Default")
      (node (ref "R95") (pin "2") (pintype "passive"))
      (node (ref "U39") (pin "3") (pintype "passive"))
    )
    (net (code "163") (name "Net-(R96-Pad1)") (class "Default")
      (node (ref "R96") (pin "1") (pintype "passive"))
      (node (ref "U40") (pin "1") (pintype "passive"))
    )
    (net (code "164") (name "Net-(R97-Pad2)") (class "Default")
      (node (ref "R97") (pin "2") (pintype "passive"))
      (node (ref "U42") (pin "4") (pintype "passive"))
    )
    (net (code "165") (name "Net-(R98-Pad2)") (class "Default")
      (node (ref "R98") (pin "2") (pinfunction "2_2") (pintype "passive"))
      (node (ref "R99") (pin "2") (pintype "passive"))
      (node (ref "U40") (pin "3") (pintype "passive"))
    )
    (net (code "166") (name "Net-(R100-Pad1)") (class "Default")
      (node (ref "R100") (pin "1") (pintype "passive"))
      (node (ref "U42") (pin "1") (pintype "passive"))
    )
    (net (code "167") (name "Net-(R101-Pad1)") (class "Default")
      (node (ref "R101") (pin "1") (pintype "passive"))
      (node (ref "U40") (pin "4") (pintype "passive"))
    )
    (net (code "168") (name "Net-(R102-Pad2)") (class "Default")
      (node (ref "R102") (pin "2") (pinfunction "2_2") (pintype "passive"))
      (node (ref "R103") (pin "2") (pintype "passive"))
      (node (ref "U42") (pin "3") (pintype "passive"))
    )
    (net (code "169") (name "Net-(R104-Pad1)") (class "Default")
      (node (ref "R104") (pin "1") (pintype "passive"))
      (node (ref "U43") (pin "1") (pintype "passive"))
    )
    (net (code "170") (name "Net-(R105-Pad2)") (class "Default")
      (node (ref "R105") (pin "2") (pintype "passive"))
      (node (ref "U43") (pin "4") (pintype "passive"))
    )
    (net (code "171") (name "Net-(R107-Pad2)") (class "Default")
      (node (ref "R107") (pin "2") (pinfunction "2_2") (pintype "passive"))
      (node (ref "R108") (pin "2") (pintype "passive"))
      (node (ref "U43") (pin "3") (pintype "passive"))
    )
    (net (code "172") (name "Net-(R109-Pad1)") (class "Default")
      (node (ref "R109") (pin "1") (pintype "passive"))
      (node (ref "U45") (pin "1") (pintype "passive"))
    )
    (net (code "173") (name "Net-(R110-Pad1)") (class "Default")
      (node (ref "R110") (pin "1") (pintype "passive"))
      (node (ref "U45") (pin "4") (pintype "passive"))
    )
    (net (code "174") (name "Net-(R111-Pad2)") (class "Default")
      (node (ref "R111") (pin "2") (pinfunction "2_2") (pintype "passive"))
      (node (ref "R112") (pin "2") (pintype "passive"))
      (node (ref "U45") (pin "3") (pintype "passive"))
    )
    (net (code "175") (name "Net-(R113-Pad1)") (class "Default")
      (node (ref "R113") (pin "1") (pintype "passive"))
      (node (ref "U46") (pin "1") (pintype "passive"))
    )
    (net (code "176") (name "Net-(R114-Pad2)") (class "Default")
      (node (ref "R114") (pin "2") (pintype "passive"))
      (node (ref "U46") (pin "4") (pintype "passive"))
    )
    (net (code "177") (name "Net-(R116-Pad2)") (class "Default")
      (node (ref "R116") (pin "2") (pinfunction "2_2") (pintype "passive"))
      (node (ref "R118") (pin "2") (pintype "passive"))
      (node (ref "U46") (pin "3") (pintype "passive"))
    )
    (net (code "178") (name "Net-(R119-Pad1)") (class "Default")
      (node (ref "R119") (pin "1") (pintype "passive"))
      (node (ref "U49") (pin "1") (pintype "passive"))
    )
    (net (code "179") (name "Net-(R120-Pad2)") (class "Default")
      (node (ref "R120") (pin "2") (pintype "passive"))
      (node (ref "U49") (pin "4") (pintype "passive"))
    )
    (net (code "180") (name "Net-(R123-Pad2)") (class "Default")
      (node (ref "R123") (pin "2") (pinfunction "2_2") (pintype "passive"))
      (node (ref "R124") (pin "2") (pintype "passive"))
      (node (ref "U49") (pin "3") (pintype "passive"))
    )
    (net (code "181") (name "Net-(R125-Pad1)") (class "Default")
      (node (ref "R125") (pin "1") (pintype "passive"))
      (node (ref "U50") (pin "1") (pintype "passive"))
    )
    (net (code "182") (name "Net-(R126-Pad2)") (class "Default")
      (node (ref "R126") (pin "2") (pintype "passive"))
      (node (ref "U53") (pin "4") (pintype "passive"))
    )
    (net (code "183") (name "Net-(R127-Pad2)") (class "Default")
      (node (ref "R127") (pin "2") (pinfunction "2_2") (pintype "passive"))
      (node (ref "R128") (pin "2") (pintype "passive"))
      (node (ref "U50") (pin "3") (pintype "passive"))
    )
    (net (code "184") (name "Net-(R130-Pad1)") (class "Default")
      (node (ref "R130") (pin "1") (pintype "passive"))
      (node (ref "U53") (pin "1") (pintype "passive"))
    )
    (net (code "185") (name "Net-(R131-Pad2)") (class "Default")
      (node (ref "R131") (pin "2") (pintype "passive"))
      (node (ref "U50") (pin "4") (pintype "passive"))
    )
    (net (code "186") (name "Net-(R133-Pad2)") (class "Default")
      (node (ref "R133") (pin "2") (pinfunction "2_2") (pintype "passive"))
      (node (ref "R135") (pin "2") (pintype "passive"))
      (node (ref "U53") (pin "3") (pintype "passive"))
    )
    (net (code "187") (name "Net-(R137-Pad1)") (class "Default")
      (node (ref "R137") (pin "1") (pintype "passive"))
      (node (ref "U54") (pin "1") (pintype "passive"))
    )
    (net (code "188") (name "Net-(R138-Pad2)") (class "Default")
      (node (ref "R138") (pin "2") (pintype "passive"))
      (node (ref "U54") (pin "4") (pintype "passive"))
    )
    (net (code "189") (name "Net-(R139-Pad2)") (class "Default")
      (node (ref "R139") (pin "2") (pinfunction "2_2") (pintype "passive"))
      (node (ref "R140") (pin "2") (pintype "passive"))
      (node (ref "U54") (pin "3") (pintype "passive"))
    )
    (net (code "190") (name "Net-(R141-Pad1)") (class "Default")
      (node (ref "R141") (pin "1") (pintype "passive"))
      (node (ref "U56") (pin "1") (pintype "passive"))
    )
    (net (code "191") (name "Net-(R142-Pad2)") (class "Default")
      (node (ref "R142") (pin "2") (pintype "passive"))
      (node (ref "U56") (pin "4") (pintype "passive"))
    )
    (net (code "192") (name "Net-(R143-Pad2)") (class "Default")
      (node (ref "R143") (pin "2") (pinfunction "2_2") (pintype "passive"))
      (node (ref "R144") (pin "2") (pintype "passive"))
      (node (ref "U56") (pin "3") (pintype "passive"))
    )
    (net (code "193") (name "Net-(U1-A1)") (class "Default")
      (node (ref "R17") (pin "1") (pintype "passive"))
      (node (ref "U1") (pin "1") (pinfunction "A1_1") (pintype "passive"))
    )
    (net (code "194") (name "Net-(U1-A2)") (class "Default")
      (node (ref "R11") (pin "1") (pintype "passive"))
      (node (ref "U1") (pin "4") (pinfunction "A2_4") (pintype "passive"))
    )
    (net (code "195") (name "Net-(U2-A1)") (class "Default")
      (node (ref "R18") (pin "1") (pintype "passive"))
      (node (ref "U2") (pin "1") (pinfunction "A1_1") (pintype "passive"))
    )
    (net (code "196") (name "Net-(U2-A2)") (class "Default")
      (node (ref "R12") (pin "1") (pintype "passive"))
      (node (ref "U2") (pin "4") (pinfunction "A2_4") (pintype "passive"))
    )
    (net (code "197") (name "Net-(U3-A1)") (class "Default")
      (node (ref "R25") (pin "1") (pintype "passive"))
      (node (ref "U3") (pin "1") (pinfunction "A1_1") (pintype "passive"))
    )
    (net (code "198") (name "Net-(U3-A2)") (class "Default")
      (node (ref "R19") (pin "1") (pintype "passive"))
      (node (ref "U3") (pin "4") (pinfunction "A2_4") (pintype "passive"))
    )
    (net (code "199") (name "Net-(U4-A1)") (class "Default")
      (node (ref "R26") (pin "1") (pintype "passive"))
      (node (ref "U4") (pin "1") (pinfunction "A1_1") (pintype "passive"))
    )
    (net (code "200") (name "Net-(U4-A2)") (class "Default")
      (node (ref "R20") (pin "1") (pintype "passive"))
      (node (ref "U4") (pin "4") (pinfunction "A2_4") (pintype "passive"))
    )
    (net (code "201") (name "Net-(U5-DACA)") (class "Default")
      (node (ref "R1") (pin "2") (pintype "passive"))
      (node (ref "U5") (pin "12") (pinfunction "DACA_12") (pintype "passive"))
    )
    (net (code "202") (name "Net-(U5-DACB)") (class "Default")
      (node (ref "R2") (pin "2") (pintype "passive"))
      (node (ref "U5") (pin "11") (pinfunction "DACB_11") (pintype "passive"))
    )
    (net (code "203") (name "Net-(U5-DACC)") (class "Default")
      (node (ref "R3") (pin "2") (pintype "passive"))
      (node (ref "U5") (pin "10") (pinfunction "DACC_10") (pintype "passive"))
    )
    (net (code "204") (name "Net-(U5-DACD)") (class "Default")
      (node (ref "R4") (pin "2") (pintype "passive"))
      (node (ref "U5") (pin "9") (pinfunction "DACD_9") (pintype "passive"))
    )
    (net (code "205") (name "Net-(U48-A1)") (class "Default")
      (node (ref "R122") (pin "1") (pintype "passive"))
      (node (ref "U48") (pin "1") (pinfunction "A1_1") (pintype "passive"))
    )
    (net (code "206") (name "Net-(U48-A2)") (class "Default")
      (node (ref "R115") (pin "1") (pintype "passive"))
      (node (ref "U48") (pin "4") (pinfunction "A2_4") (pintype "passive"))
    )
    (net (code "207") (name "Net-(U52-A1)") (class "Default")
      (node (ref "R136") (pin "1") (pintype "passive"))
      (node (ref "U52") (pin "1") (pinfunction "A1_1") (pintype "passive"))
    )
    (net (code "208") (name "Net-(U52-A2)") (class "Default")
      (node (ref "R129") (pin "1") (pintype "passive"))
      (node (ref "U52") (pin "4") (pinfunction "A2_4") (pintype "passive"))
    )
    (net (code "209") (name "PW_VCC") (class "Default")
      (node (ref "D1") (pin "1") (pinfunction "A_1") (pintype "passive"))
      (node (ref "J4") (pin "1") (pinfunction "1_1") (pintype "passive"))
    )
    (net (code "210") (name "VCC3.3_B") (class "Default")
      (node (ref "P36") (pin "32") (pinfunction "32_32") (pintype "passive"))
      (node (ref "P44") (pin "3") (pinfunction "3_3") (pintype "passive"))
      (node (ref "P46") (pin "3") (pinfunction "3_3") (pintype "passive"))
      (node (ref "R100") (pin "2") (pintype "passive"))
      (node (ref "R104") (pin "2") (pintype "passive"))
      (node (ref "R109") (pin "2") (pintype "passive"))
      (node (ref "R11") (pin "2") (pintype "passive"))
      (node (ref "R113") (pin "2") (pintype "passive"))
      (node (ref "R115") (pin "2") (pintype "passive"))
      (node (ref "R119") (pin "2") (pintype "passive"))
      (node (ref "R12") (pin "2") (pintype "passive"))
      (node (ref "R122") (pin "2") (pintype "passive"))
      (node (ref "R125") (pin "2") (pintype "passive"))
      (node (ref "R129") (pin "2") (pintype "passive"))
      (node (ref "R13") (pin "2") (pintype "passive"))
      (node (ref "R130") (pin "2") (pintype "passive"))
      (node (ref "R136") (pin "2") (pintype "passive"))
      (node (ref "R137") (pin "2") (pintype "passive"))
      (node (ref "R14") (pin "2") (pintype "passive"))
      (node (ref "R141") (pin "2") (pintype "passive"))
      (node (ref "R15") (pin "1") (pintype "passive"))
      (node (ref "R16") (pin "1") (pintype "passive"))
      (node (ref "R17") (pin "2") (pintype "passive"))
      (node (ref "R18") (pin "2") (pintype "passive"))
      (node (ref "R19") (pin "2") (pintype "passive"))
      (node (ref "R20") (pin "2") (pintype "passive"))
      (node (ref "R21") (pin "2") (pintype "passive"))
      (node (ref "R22") (pin "2") (pintype "passive"))
      (node (ref "R23") (pin "1") (pintype "passive"))
      (node (ref "R24") (pin "1") (pintype "passive"))
      (node (ref "R25") (pin "2") (pintype "passive"))
      (node (ref "R26") (pin "2") (pintype "passive"))
      (node (ref "R42") (pin "2") (pintype "passive"))
      (node (ref "R44") (pin "2") (pintype "passive"))
      (node (ref "R49") (pin "2") (pintype "passive"))
      (node (ref "R50") (pin "2") (pintype "passive"))
      (node (ref "R53") (pin "2") (pintype "passive"))
      (node (ref "R57") (pin "2") (pintype "passive"))
      (node (ref "R58") (pin "2") (pintype "passive"))
      (node (ref "R60") (pin "2") (pintype "passive"))
      (node (ref "R65") (pin "2") (pintype "passive"))
      (node (ref "R66") (pin "2") (pintype "passive"))
      (node (ref "R68") (pin "2") (pintype "passive"))
      (node (ref "R74") (pin "2") (pintype "passive"))
      (node (ref "R76") (pin "2") (pintype "passive"))
      (node (ref "R82") (pin "2") (pintype "passive"))
      (node (ref "R84") (pin "2") (pintype "passive"))
      (node (ref "R86") (pin "2") (pintype "passive"))
      (node (ref "R88") (pin "2") (pintype "passive"))
      (node (ref "R90") (pin "2") (pintype "passive"))
      (node (ref "R92") (pin "2") (pintype "passive"))
      (node (ref "R94") (pin "2") (pintype "passive"))
      (node (ref "R96") (pin "2") (pintype "passive"))
      (node (ref "U5") (pin "2") (pinfunction "REFA_2") (pintype "passive"))
      (node (ref "U5") (pin "3") (pinfunction "REFB_3") (pintype "passive"))
      (node (ref "U5") (pin "4") (pinfunction "REFC_4") (pintype "passive"))
      (node (ref "U5") (pin "5") (pinfunction "REFD_5") (pintype "passive"))
    )
    (net (code "211") (name "VCC5") (class "Default")
      (node (ref "P36") (pin "31") (pinfunction "31_31") (pintype "passive"))
      (node (ref "R117") (pin "2") (pintype "passive"))
      (node (ref "R121") (pin "1") (pintype "passive"))
      (node (ref "R132") (pin "2") (pintype "passive"))
      (node (ref "R134") (pin "1") (pintype "passive"))
      (node (ref "R43") (pin "2") (pintype "passive"))
      (node (ref "R45") (pin "2") (pintype "passive"))
      (node (ref "R54") (pin "2") (pintype "passive"))
      (node (ref "R61") (pin "2") (pintype "passive"))
      (node (ref "R69") (pin "2") (pintype "passive"))
      (node (ref "R77") (pin "2") (pintype "passive"))
      (node (ref "R85") (pin "2") (pintype "passive"))
      (node (ref "R87") (pin "2") (pintype "passive"))
      (node (ref "R89") (pin "2") (pintype "passive"))
      (node (ref "R91") (pin "2") (pintype "passive"))
      (node (ref "R93") (pin "2") (pintype "passive"))
      (node (ref "U1") (pin "8") (pinfunction "VCC_8") (pintype "passive"))
      (node (ref "U2") (pin "8") (pinfunction "VCC_8") (pintype "passive"))
      (node (ref "U3") (pin "8") (pinfunction "VCC_8") (pintype "passive"))
      (node (ref "U39") (pin "4") (pintype "passive"))
      (node (ref "U4") (pin "8") (pinfunction "VCC_8") (pintype "passive"))
      (node (ref "U48") (pin "8") (pinfunction "VCC_8") (pintype "passive"))
      (node (ref "U5") (pin "14") (pinfunction "VDD_14") (pintype "passive"))
      (node (ref "U52") (pin "8") (pinfunction "VCC_8") (pintype "passive"))
    )
    (net (code "212") (name "VCC24_B") (class "Default")
      (node (ref "C2") (pin "1") (pinfunction "VCC_1") (pintype "passive"))
      (node (ref "C3") (pin "1") (pintype "passive"))
      (node (ref "D39") (pin "A") (pinfunction "A_A") (pintype "passive"))
      (node (ref "D40") (pin "A") (pinfunction "A_A") (pintype "passive"))
      (node (ref "D42") (pin "A") (pinfunction "A_A") (pintype "passive"))
      (node (ref "D43") (pin "A") (pinfunction "A_A") (pintype "passive"))
      (node (ref "D44") (pin "2") (pinfunction "K_2") (pintype "passive"))
      (node (ref "D45") (pin "2") (pinfunction "K_2") (pintype "passive"))
      (node (ref "D46") (pin "2") (pinfunction "K_2") (pintype "passive"))
      (node (ref "D47") (pin "2") (pinfunction "K_2") (pintype "passive"))
      (node (ref "D48") (pin "2") (pinfunction "K_2") (pintype "passive"))
      (node (ref "D49") (pin "A") (pinfunction "A_A") (pintype "passive"))
      (node (ref "D50") (pin "2") (pinfunction "K_2") (pintype "passive"))
      (node (ref "D51") (pin "A") (pinfunction "A_A") (pintype "passive"))
      (node (ref "D52") (pin "2") (pinfunction "K_2") (pintype "passive"))
      (node (ref "D53") (pin "2") (pinfunction "K_2") (pintype "passive"))
      (node (ref "D54") (pin "A") (pinfunction "A_A") (pintype "passive"))
      (node (ref "D55") (pin "2") (pinfunction "K_2") (pintype "passive"))
      (node (ref "D56") (pin "2") (pinfunction "K_2") (pintype "passive"))
      (node (ref "D57") (pin "A") (pinfunction "A_A") (pintype "passive"))
      (node (ref "D58") (pin "A") (pinfunction "A_A") (pintype "passive"))
      (node (ref "D59") (pin "A") (pinfunction "A_A") (pintype "passive"))
      (node (ref "F1") (pin "2") (pinfunction "2_2") (pintype "passive"))
      (node (ref "P1") (pin "1") (pinfunction "1_1") (pintype "passive"))
      (node (ref "P2") (pin "1") (pinfunction "1_1") (pintype "passive"))
      (node (ref "P36") (pin "1") (pinfunction "1_1") (pintype "passive"))
      (node (ref "P38") (pin "1") (pinfunction "1_1") (pintype "passive"))
      (node (ref "P4") (pin "1") (pinfunction "1_1") (pintype "passive"))
      (node (ref "P48") (pin "1") (pinfunction "1_1") (pintype "passive"))
      (node (ref "P53") (pin "1") (pinfunction "1_1") (pintype "passive"))
      (node (ref "P60") (pin "1") (pinfunction "1_1") (pintype "passive"))
      (node (ref "P61") (pin "1") (pinfunction "1_1") (pintype "passive"))
      (node (ref "P62") (pin "1") (pinfunction "1_1") (pintype "passive"))
      (node (ref "R106") (pin "1") (pinfunction "1_1") (pintype "passive"))
      (node (ref "R46") (pin "2") (pintype "passive"))
      (node (ref "R47") (pin "2") (pintype "passive"))
      (node (ref "R5") (pin "1") (pintype "passive"))
      (node (ref "R52") (pin "2") (pintype "passive"))
      (node (ref "R55") (pin "2") (pintype "passive"))
      (node (ref "R6") (pin "2") (pintype "passive"))
      (node (ref "R62") (pin "2") (pintype "passive"))
      (node (ref "R63") (pin "2") (pintype "passive"))
      (node (ref "R7") (pin "1") (pintype "passive"))
      (node (ref "R71") (pin "2") (pintype "passive"))
      (node (ref "R79") (pin "2") (pintype "passive"))
      (node (ref "R8") (pin "2") (pintype "passive"))
    )
  )
)
